# Control_Logic_V2.net
KiCad netlist of a schematic drawn in EAGLE
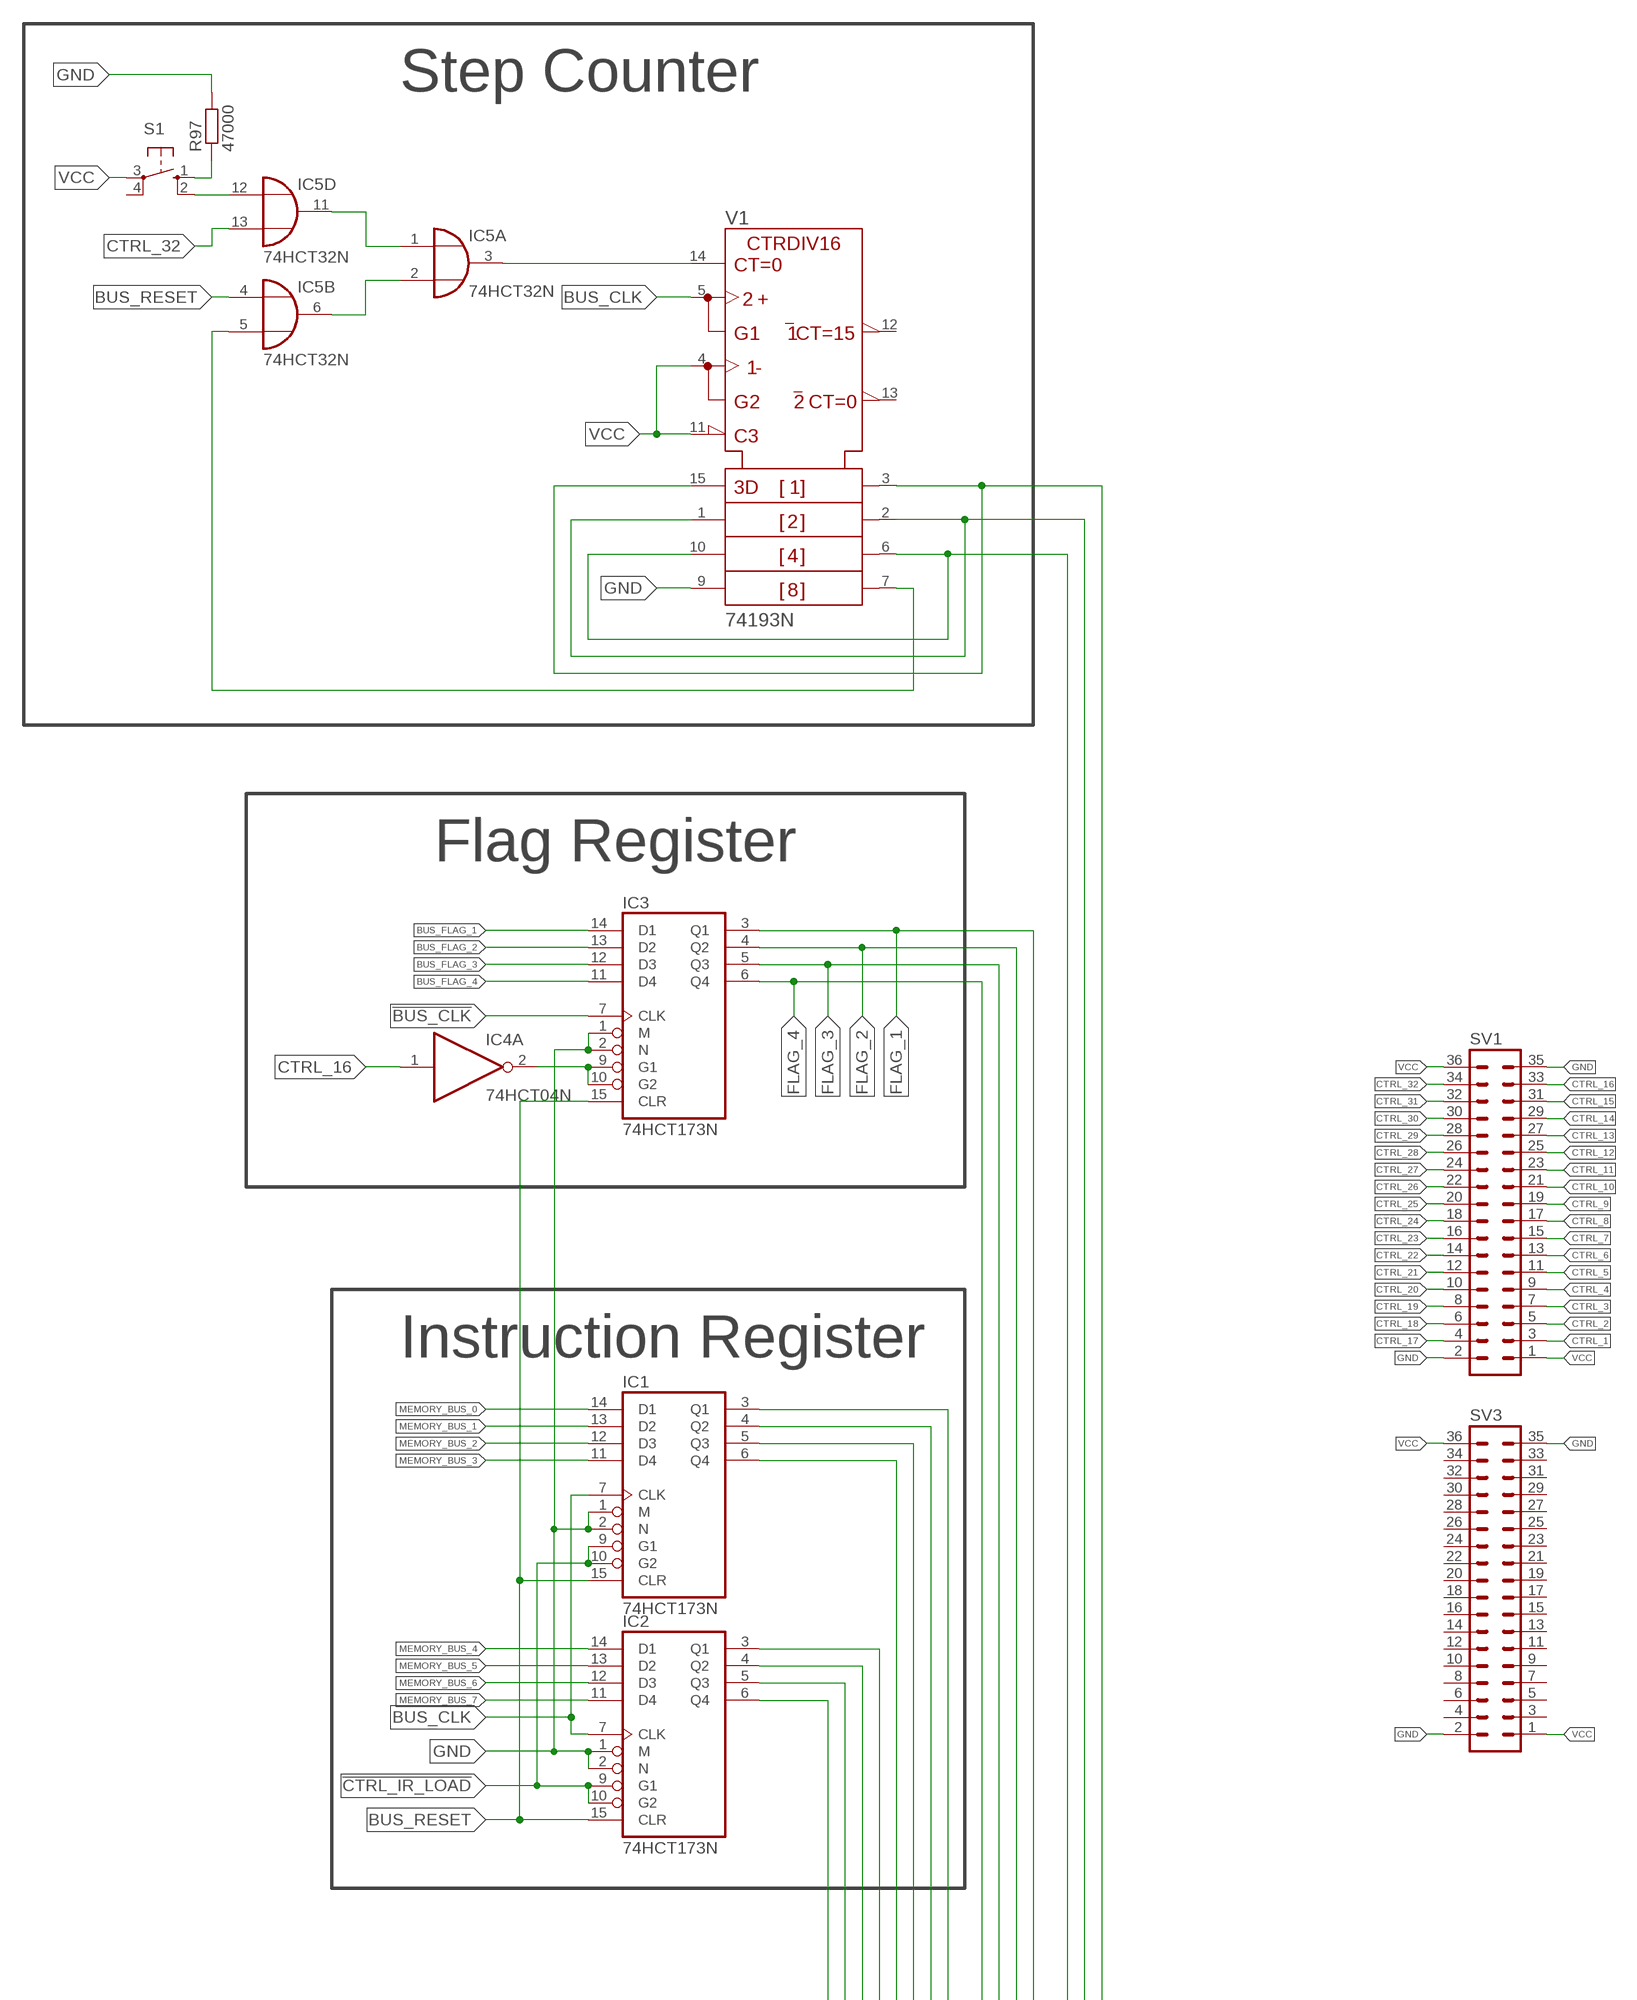
[diagram p0: schematic, sheet 1, part 1 of 3]
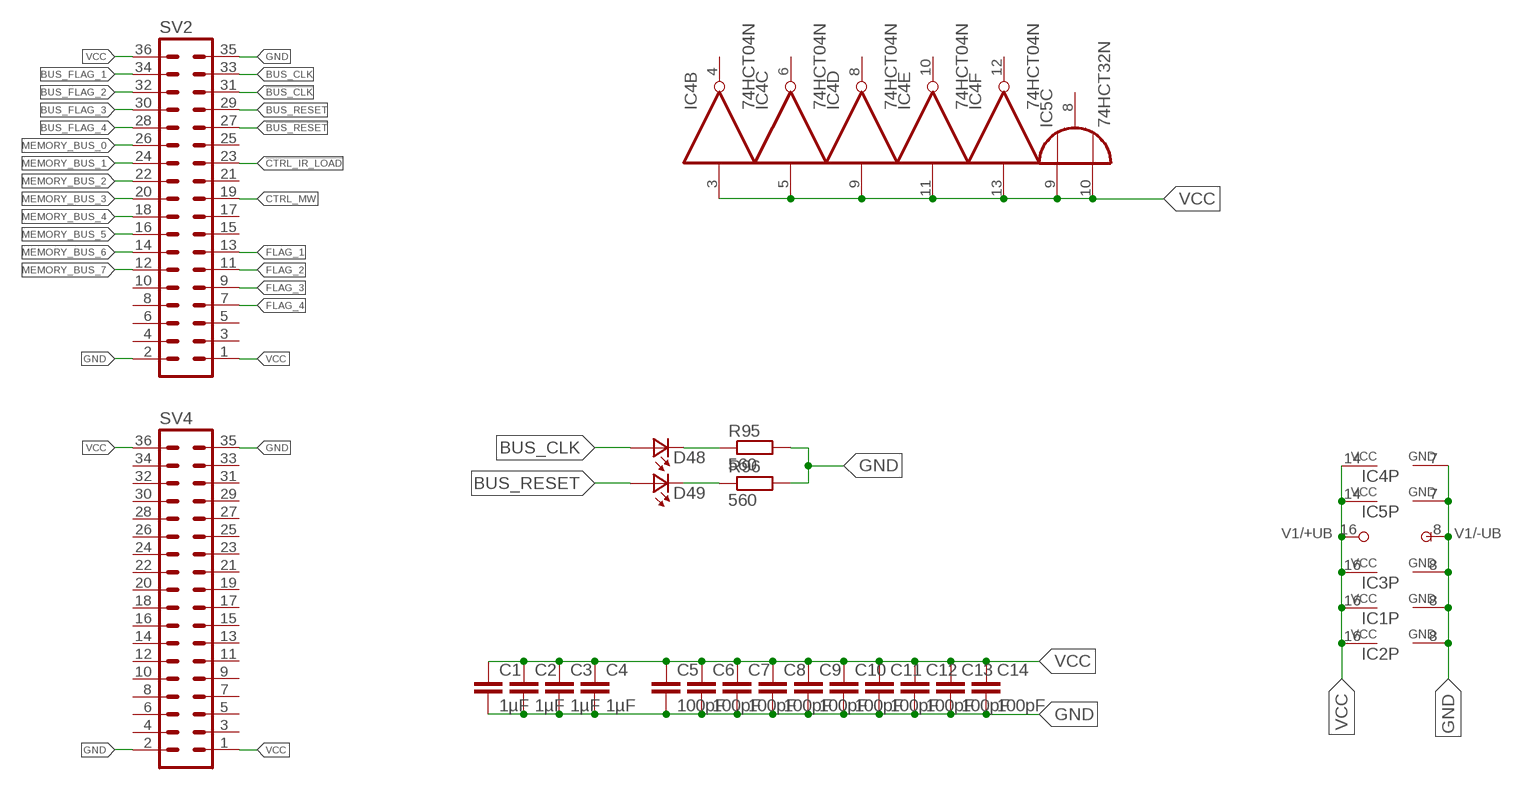
[diagram p1: schematic, sheet 1, part 2 of 3]
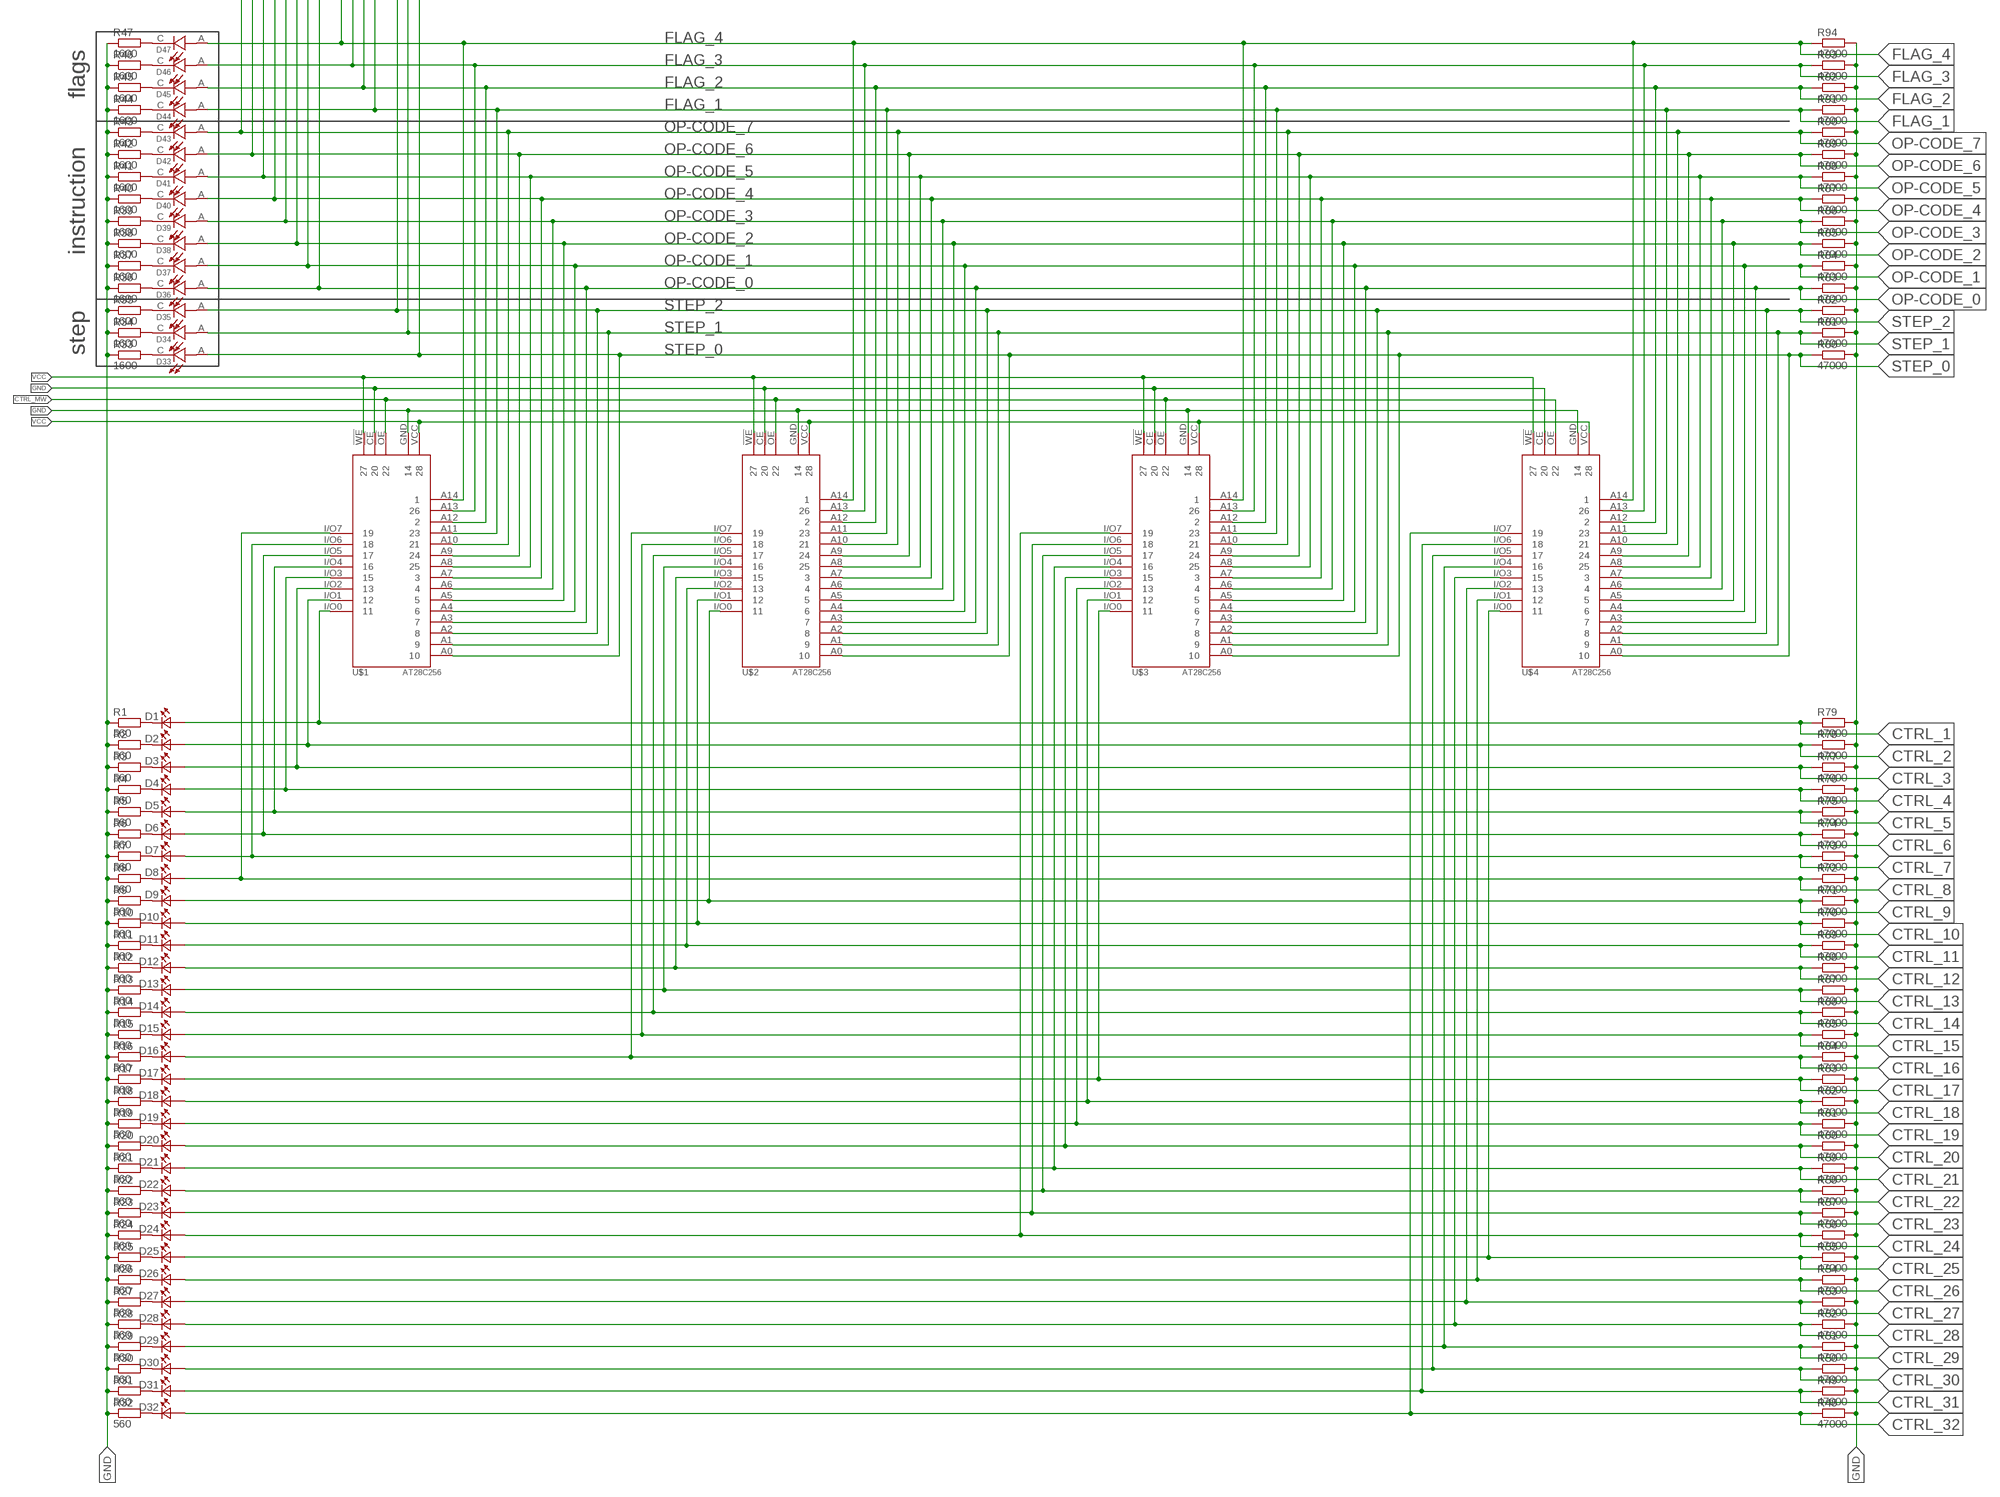
[diagram p2: schematic, sheet 1, part 3 of 3]

(export (version "E")
  (design (tool "Eeschema 10.0.6"))
  (components
    (comp (ref "C1")
      (value "1µF")
      (footprint "eagle-import:C0805")
      (libsource (lib "eagle-import") (part "C-EUC0805"))
    )
    (comp (ref "C2")
      (value "1µF")
      (footprint "eagle-import:C0805")
      (libsource (lib "eagle-import") (part "C-EUC0805"))
    )
    (comp (ref "C3")
      (value "1µF")
      (footprint "eagle-import:C0805")
      (libsource (lib "eagle-import") (part "C-EUC0805"))
    )
    (comp (ref "C4")
      (value "1µF")
      (footprint "eagle-import:C0805")
      (libsource (lib "eagle-import") (part "C-EUC0805"))
    )
    (comp (ref "C5")
      (value "100pF")
      (footprint "eagle-import:C0805")
      (libsource (lib "eagle-import") (part "C-EUC0805"))
    )
    (comp (ref "C6")
      (value "100pF")
      (footprint "eagle-import:C0805")
      (libsource (lib "eagle-import") (part "C-EUC0805"))
    )
    (comp (ref "C7")
      (value "100pF")
      (footprint "eagle-import:C0805")
      (libsource (lib "eagle-import") (part "C-EUC0805"))
    )
    (comp (ref "C8")
      (value "100pF")
      (footprint "eagle-import:C0805")
      (libsource (lib "eagle-import") (part "C-EUC0805"))
    )
    (comp (ref "C9")
      (value "100pF")
      (footprint "eagle-import:C0805")
      (libsource (lib "eagle-import") (part "C-EUC0805"))
    )
    (comp (ref "C10")
      (value "100pF")
      (footprint "eagle-import:C0805")
      (libsource (lib "eagle-import") (part "C-EUC0805"))
    )
    (comp (ref "C11")
      (value "100pF")
      (footprint "eagle-import:C0805")
      (libsource (lib "eagle-import") (part "C-EUC0805"))
    )
    (comp (ref "C12")
      (value "100pF")
      (footprint "eagle-import:C0805")
      (libsource (lib "eagle-import") (part "C-EUC0805"))
    )
    (comp (ref "C13")
      (value "100pF")
      (footprint "eagle-import:C0805")
      (libsource (lib "eagle-import") (part "C-EUC0805"))
    )
    (comp (ref "C14")
      (value "100pF")
      (footprint "eagle-import:C0805")
      (libsource (lib "eagle-import") (part "C-EUC0805"))
    )
    (comp (ref "D1")
      (value "LTST-C193TBKT-5A")
      (footprint "eagle-import:0603")
      (libsource (lib "eagle-import") (part "LTST-C193TBKT-5A"))
    )
    (comp (ref "D2")
      (value "LTST-C193TBKT-5A")
      (footprint "eagle-import:0603")
      (libsource (lib "eagle-import") (part "LTST-C193TBKT-5A"))
    )
    (comp (ref "D3")
      (value "LTST-C193TBKT-5A")
      (footprint "eagle-import:0603")
      (libsource (lib "eagle-import") (part "LTST-C193TBKT-5A"))
    )
    (comp (ref "D4")
      (value "LTST-C193TBKT-5A")
      (footprint "eagle-import:0603")
      (libsource (lib "eagle-import") (part "LTST-C193TBKT-5A"))
    )
    (comp (ref "D5")
      (value "LTST-C193TBKT-5A")
      (footprint "eagle-import:0603")
      (libsource (lib "eagle-import") (part "LTST-C193TBKT-5A"))
    )
    (comp (ref "D6")
      (value "LTST-C193TBKT-5A")
      (footprint "eagle-import:0603")
      (libsource (lib "eagle-import") (part "LTST-C193TBKT-5A"))
    )
    (comp (ref "D7")
      (value "LTST-C193TBKT-5A")
      (footprint "eagle-import:0603")
      (libsource (lib "eagle-import") (part "LTST-C193TBKT-5A"))
    )
    (comp (ref "D8")
      (value "LTST-C193TBKT-5A")
      (footprint "eagle-import:0603")
      (libsource (lib "eagle-import") (part "LTST-C193TBKT-5A"))
    )
    (comp (ref "D9")
      (value "LTST-C193TBKT-5A")
      (footprint "eagle-import:0603")
      (libsource (lib "eagle-import") (part "LTST-C193TBKT-5A"))
    )
    (comp (ref "D10")
      (value "LTST-C193TBKT-5A")
      (footprint "eagle-import:0603")
      (libsource (lib "eagle-import") (part "LTST-C193TBKT-5A"))
    )
    (comp (ref "D11")
      (value "LTST-C193TBKT-5A")
      (footprint "eagle-import:0603")
      (libsource (lib "eagle-import") (part "LTST-C193TBKT-5A"))
    )
    (comp (ref "D12")
      (value "LTST-C193TBKT-5A")
      (footprint "eagle-import:0603")
      (libsource (lib "eagle-import") (part "LTST-C193TBKT-5A"))
    )
    (comp (ref "D13")
      (value "LTST-C193TBKT-5A")
      (footprint "eagle-import:0603")
      (libsource (lib "eagle-import") (part "LTST-C193TBKT-5A"))
    )
    (comp (ref "D14")
      (value "LTST-C193TBKT-5A")
      (footprint "eagle-import:0603")
      (libsource (lib "eagle-import") (part "LTST-C193TBKT-5A"))
    )
    (comp (ref "D15")
      (value "LTST-C193TBKT-5A")
      (footprint "eagle-import:0603")
      (libsource (lib "eagle-import") (part "LTST-C193TBKT-5A"))
    )
    (comp (ref "D16")
      (value "LTST-C193TBKT-5A")
      (footprint "eagle-import:0603")
      (libsource (lib "eagle-import") (part "LTST-C193TBKT-5A"))
    )
    (comp (ref "D17")
      (value "LTST-C193TBKT-5A")
      (footprint "eagle-import:0603")
      (libsource (lib "eagle-import") (part "LTST-C193TBKT-5A"))
    )
    (comp (ref "D18")
      (value "LTST-C193TBKT-5A")
      (footprint "eagle-import:0603")
      (libsource (lib "eagle-import") (part "LTST-C193TBKT-5A"))
    )
    (comp (ref "D19")
      (value "LTST-C193TBKT-5A")
      (footprint "eagle-import:0603")
      (libsource (lib "eagle-import") (part "LTST-C193TBKT-5A"))
    )
    (comp (ref "D20")
      (value "LTST-C193TBKT-5A")
      (footprint "eagle-import:0603")
      (libsource (lib "eagle-import") (part "LTST-C193TBKT-5A"))
    )
    (comp (ref "D21")
      (value "LTST-C193TBKT-5A")
      (footprint "eagle-import:0603")
      (libsource (lib "eagle-import") (part "LTST-C193TBKT-5A"))
    )
    (comp (ref "D22")
      (value "LTST-C193TBKT-5A")
      (footprint "eagle-import:0603")
      (libsource (lib "eagle-import") (part "LTST-C193TBKT-5A"))
    )
    (comp (ref "D23")
      (value "LTST-C193TBKT-5A")
      (footprint "eagle-import:0603")
      (libsource (lib "eagle-import") (part "LTST-C193TBKT-5A"))
    )
    (comp (ref "D24")
      (value "LTST-C193TBKT-5A")
      (footprint "eagle-import:0603")
      (libsource (lib "eagle-import") (part "LTST-C193TBKT-5A"))
    )
    (comp (ref "D25")
      (value "LTST-C193TBKT-5A")
      (footprint "eagle-import:0603")
      (libsource (lib "eagle-import") (part "LTST-C193TBKT-5A"))
    )
    (comp (ref "D26")
      (value "LTST-C193TBKT-5A")
      (footprint "eagle-import:0603")
      (libsource (lib "eagle-import") (part "LTST-C193TBKT-5A"))
    )
    (comp (ref "D27")
      (value "LTST-C193TBKT-5A")
      (footprint "eagle-import:0603")
      (libsource (lib "eagle-import") (part "LTST-C193TBKT-5A"))
    )
    (comp (ref "D28")
      (value "LTST-C193TBKT-5A")
      (footprint "eagle-import:0603")
      (libsource (lib "eagle-import") (part "LTST-C193TBKT-5A"))
    )
    (comp (ref "D29")
      (value "LTST-C193TBKT-5A")
      (footprint "eagle-import:0603")
      (libsource (lib "eagle-import") (part "LTST-C193TBKT-5A"))
    )
    (comp (ref "D30")
      (value "LTST-C193TBKT-5A")
      (footprint "eagle-import:0603")
      (libsource (lib "eagle-import") (part "LTST-C193TBKT-5A"))
    )
    (comp (ref "D31")
      (value "LTST-C193TBKT-5A")
      (footprint "eagle-import:0603")
      (libsource (lib "eagle-import") (part "LTST-C193TBKT-5A"))
    )
    (comp (ref "D32")
      (value "LTST-C193TBKT-5A")
      (footprint "eagle-import:0603")
      (libsource (lib "eagle-import") (part "LTST-C193TBKT-5A"))
    )
    (comp (ref "D33")
      (value "LTST-C193KRKT-5A")
      (footprint "eagle-import:LEDC1608X45N")
      (fields (field (name "MANUFACTURER") "Lite-On"))
      (libsource (lib "eagle-import") (part "LTST-C193KRKT-5A"))
    )
    (comp (ref "D34")
      (value "LTST-C193KRKT-5A")
      (footprint "eagle-import:LEDC1608X45N")
      (fields (field (name "MANUFACTURER") "Lite-On"))
      (libsource (lib "eagle-import") (part "LTST-C193KRKT-5A"))
    )
    (comp (ref "D35")
      (value "LTST-C193KRKT-5A")
      (footprint "eagle-import:LEDC1608X45N")
      (fields (field (name "MANUFACTURER") "Lite-On"))
      (libsource (lib "eagle-import") (part "LTST-C193KRKT-5A"))
    )
    (comp (ref "D36")
      (value "LTST-C193KRKT-5A")
      (footprint "eagle-import:LEDC1608X45N")
      (fields (field (name "MANUFACTURER") "Lite-On"))
      (libsource (lib "eagle-import") (part "LTST-C193KRKT-5A"))
    )
    (comp (ref "D37")
      (value "LTST-C193KRKT-5A")
      (footprint "eagle-import:LEDC1608X45N")
      (fields (field (name "MANUFACTURER") "Lite-On"))
      (libsource (lib "eagle-import") (part "LTST-C193KRKT-5A"))
    )
    (comp (ref "D38")
      (value "LTST-C193KRKT-5A")
      (footprint "eagle-import:LEDC1608X45N")
      (fields (field (name "MANUFACTURER") "Lite-On"))
      (libsource (lib "eagle-import") (part "LTST-C193KRKT-5A"))
    )
    (comp (ref "D39")
      (value "LTST-C193KRKT-5A")
      (footprint "eagle-import:LEDC1608X45N")
      (fields (field (name "MANUFACTURER") "Lite-On"))
      (libsource (lib "eagle-import") (part "LTST-C193KRKT-5A"))
    )
    (comp (ref "D40")
      (value "LTST-C193KRKT-5A")
      (footprint "eagle-import:LEDC1608X45N")
      (fields (field (name "MANUFACTURER") "Lite-On"))
      (libsource (lib "eagle-import") (part "LTST-C193KRKT-5A"))
    )
    (comp (ref "D41")
      (value "LTST-C193KRKT-5A")
      (footprint "eagle-import:LEDC1608X45N")
      (fields (field (name "MANUFACTURER") "Lite-On"))
      (libsource (lib "eagle-import") (part "LTST-C193KRKT-5A"))
    )
    (comp (ref "D42")
      (value "LTST-C193KRKT-5A")
      (footprint "eagle-import:LEDC1608X45N")
      (fields (field (name "MANUFACTURER") "Lite-On"))
      (libsource (lib "eagle-import") (part "LTST-C193KRKT-5A"))
    )
    (comp (ref "D43")
      (value "LTST-C193KRKT-5A")
      (footprint "eagle-import:LEDC1608X45N")
      (fields (field (name "MANUFACTURER") "Lite-On"))
      (libsource (lib "eagle-import") (part "LTST-C193KRKT-5A"))
    )
    (comp (ref "D44")
      (value "LTST-C193KRKT-5A")
      (footprint "eagle-import:LEDC1608X45N")
      (fields (field (name "MANUFACTURER") "Lite-On"))
      (libsource (lib "eagle-import") (part "LTST-C193KRKT-5A"))
    )
    (comp (ref "D45")
      (value "LTST-C193KRKT-5A")
      (footprint "eagle-import:LEDC1608X45N")
      (fields (field (name "MANUFACTURER") "Lite-On"))
      (libsource (lib "eagle-import") (part "LTST-C193KRKT-5A"))
    )
    (comp (ref "D46")
      (value "LTST-C193KRKT-5A")
      (footprint "eagle-import:LEDC1608X45N")
      (fields (field (name "MANUFACTURER") "Lite-On"))
      (libsource (lib "eagle-import") (part "LTST-C193KRKT-5A"))
    )
    (comp (ref "D47")
      (value "LTST-C193KRKT-5A")
      (footprint "eagle-import:LEDC1608X45N")
      (fields (field (name "MANUFACTURER") "Lite-On"))
      (libsource (lib "eagle-import") (part "LTST-C193KRKT-5A"))
    )
    (comp (ref "D48")
      (value "LTST-C193TBKT-5A")
      (footprint "eagle-import:0603")
      (libsource (lib "eagle-import") (part "LTST-C193TBKT-5A"))
    )
    (comp (ref "D49")
      (value "LTST-C193TBKT-5A")
      (footprint "eagle-import:0603")
      (libsource (lib "eagle-import") (part "LTST-C193TBKT-5A"))
    )
    (comp (ref "IC1")
      (value "74HCT173N")
      (footprint "eagle-import:DIL16")
      (libsource (lib "eagle-import") (part "74173NHCT"))
    )
    (comp (ref "IC2")
      (value "74HCT173N")
      (footprint "eagle-import:DIL16")
      (libsource (lib "eagle-import") (part "74173NHCT"))
    )
    (comp (ref "IC3")
      (value "74HCT173N")
      (footprint "eagle-import:DIL16")
      (libsource (lib "eagle-import") (part "74173NHCT"))
    )
    (comp (ref "IC4")
      (value "74HCT04N")
      (footprint "eagle-import:DIL14")
      (libsource (lib "eagle-import") (part "7404NHCT"))
    )
    (comp (ref "IC5")
      (value "74HCT32N")
      (footprint "eagle-import:DIL14")
      (libsource (lib "eagle-import") (part "7432NHCT"))
    )
    (comp (ref "R1")
      (value "560")
      (footprint "eagle-import:R0805")
      (libsource (lib "eagle-import") (part "R-EU_R0805"))
    )
    (comp (ref "R2")
      (value "560")
      (footprint "eagle-import:R0805")
      (libsource (lib "eagle-import") (part "R-EU_R0805"))
    )
    (comp (ref "R3")
      (value "560")
      (footprint "eagle-import:R0805")
      (libsource (lib "eagle-import") (part "R-EU_R0805"))
    )
    (comp (ref "R4")
      (value "560")
      (footprint "eagle-import:R0805")
      (libsource (lib "eagle-import") (part "R-EU_R0805"))
    )
    (comp (ref "R5")
      (value "560")
      (footprint "eagle-import:R0805")
      (libsource (lib "eagle-import") (part "R-EU_R0805"))
    )
    (comp (ref "R6")
      (value "560")
      (footprint "eagle-import:R0805")
      (libsource (lib "eagle-import") (part "R-EU_R0805"))
    )
    (comp (ref "R7")
      (value "560")
      (footprint "eagle-import:R0805")
      (libsource (lib "eagle-import") (part "R-EU_R0805"))
    )
    (comp (ref "R8")
      (value "560")
      (footprint "eagle-import:R0805")
      (libsource (lib "eagle-import") (part "R-EU_R0805"))
    )
    (comp (ref "R9")
      (value "560")
      (footprint "eagle-import:R0805")
      (libsource (lib "eagle-import") (part "R-EU_R0805"))
    )
    (comp (ref "R10")
      (value "560")
      (footprint "eagle-import:R0805")
      (libsource (lib "eagle-import") (part "R-EU_R0805"))
    )
    (comp (ref "R11")
      (value "560")
      (footprint "eagle-import:R0805")
      (libsource (lib "eagle-import") (part "R-EU_R0805"))
    )
    (comp (ref "R12")
      (value "560")
      (footprint "eagle-import:R0805")
      (libsource (lib "eagle-import") (part "R-EU_R0805"))
    )
    (comp (ref "R13")
      (value "560")
      (footprint "eagle-import:R0805")
      (libsource (lib "eagle-import") (part "R-EU_R0805"))
    )
    (comp (ref "R14")
      (value "560")
      (footprint "eagle-import:R0805")
      (libsource (lib "eagle-import") (part "R-EU_R0805"))
    )
    (comp (ref "R15")
      (value "560")
      (footprint "eagle-import:R0805")
      (libsource (lib "eagle-import") (part "R-EU_R0805"))
    )
    (comp (ref "R16")
      (value "560")
      (footprint "eagle-import:R0805")
      (libsource (lib "eagle-import") (part "R-EU_R0805"))
    )
    (comp (ref "R17")
      (value "560")
      (footprint "eagle-import:R0805")
      (libsource (lib "eagle-import") (part "R-EU_R0805"))
    )
    (comp (ref "R18")
      (value "560")
      (footprint "eagle-import:R0805")
      (libsource (lib "eagle-import") (part "R-EU_R0805"))
    )
    (comp (ref "R19")
      (value "560")
      (footprint "eagle-import:R0805")
      (libsource (lib "eagle-import") (part "R-EU_R0805"))
    )
    (comp (ref "R20")
      (value "560")
      (footprint "eagle-import:R0805")
      (libsource (lib "eagle-import") (part "R-EU_R0805"))
    )
    (comp (ref "R21")
      (value "560")
      (footprint "eagle-import:R0805")
      (libsource (lib "eagle-import") (part "R-EU_R0805"))
    )
    (comp (ref "R22")
      (value "560")
      (footprint "eagle-import:R0805")
      (libsource (lib "eagle-import") (part "R-EU_R0805"))
    )
    (comp (ref "R23")
      (value "560")
      (footprint "eagle-import:R0805")
      (libsource (lib "eagle-import") (part "R-EU_R0805"))
    )
    (comp (ref "R24")
      (value "560")
      (footprint "eagle-import:R0805")
      (libsource (lib "eagle-import") (part "R-EU_R0805"))
    )
    (comp (ref "R25")
      (value "560")
      (footprint "eagle-import:R0805")
      (libsource (lib "eagle-import") (part "R-EU_R0805"))
    )
    (comp (ref "R26")
      (value "560")
      (footprint "eagle-import:R0805")
      (libsource (lib "eagle-import") (part "R-EU_R0805"))
    )
    (comp (ref "R27")
      (value "560")
      (footprint "eagle-import:R0805")
      (libsource (lib "eagle-import") (part "R-EU_R0805"))
    )
    (comp (ref "R28")
      (value "560")
      (footprint "eagle-import:R0805")
      (libsource (lib "eagle-import") (part "R-EU_R0805"))
    )
    (comp (ref "R29")
      (value "560")
      (footprint "eagle-import:R0805")
      (libsource (lib "eagle-import") (part "R-EU_R0805"))
    )
    (comp (ref "R30")
      (value "560")
      (footprint "eagle-import:R0805")
      (libsource (lib "eagle-import") (part "R-EU_R0805"))
    )
    (comp (ref "R31")
      (value "560")
      (footprint "eagle-import:R0805")
      (libsource (lib "eagle-import") (part "R-EU_R0805"))
    )
    (comp (ref "R32")
      (value "560")
      (footprint "eagle-import:R0805")
      (libsource (lib "eagle-import") (part "R-EU_R0805"))
    )
    (comp (ref "R33")
      (value "1600")
      (footprint "eagle-import:R0805")
      (libsource (lib "eagle-import") (part "R-EU_R0805"))
    )
    (comp (ref "R34")
      (value "1600")
      (footprint "eagle-import:R0805")
      (libsource (lib "eagle-import") (part "R-EU_R0805"))
    )
    (comp (ref "R35")
      (value "1600")
      (footprint "eagle-import:R0805")
      (libsource (lib "eagle-import") (part "R-EU_R0805"))
    )
    (comp (ref "R36")
      (value "1600")
      (footprint "eagle-import:R0805")
      (libsource (lib "eagle-import") (part "R-EU_R0805"))
    )
    (comp (ref "R37")
      (value "1600")
      (footprint "eagle-import:R0805")
      (libsource (lib "eagle-import") (part "R-EU_R0805"))
    )
    (comp (ref "R38")
      (value "1600")
      (footprint "eagle-import:R0805")
      (libsource (lib "eagle-import") (part "R-EU_R0805"))
    )
    (comp (ref "R39")
      (value "1600")
      (footprint "eagle-import:R0805")
      (libsource (lib "eagle-import") (part "R-EU_R0805"))
    )
    (comp (ref "R40")
      (value "1600")
      (footprint "eagle-import:R0805")
      (libsource (lib "eagle-import") (part "R-EU_R0805"))
    )
    (comp (ref "R41")
      (value "1600")
      (footprint "eagle-import:R0805")
      (libsource (lib "eagle-import") (part "R-EU_R0805"))
    )
    (comp (ref "R42")
      (value "1600")
      (footprint "eagle-import:R0805")
      (libsource (lib "eagle-import") (part "R-EU_R0805"))
    )
    (comp (ref "R43")
      (value "1600")
      (footprint "eagle-import:R0805")
      (libsource (lib "eagle-import") (part "R-EU_R0805"))
    )
    (comp (ref "R44")
      (value "1600")
      (footprint "eagle-import:R0805")
      (libsource (lib "eagle-import") (part "R-EU_R0805"))
    )
    (comp (ref "R45")
      (value "1600")
      (footprint "eagle-import:R0805")
      (libsource (lib "eagle-import") (part "R-EU_R0805"))
    )
    (comp (ref "R46")
      (value "1600")
      (footprint "eagle-import:R0805")
      (libsource (lib "eagle-import") (part "R-EU_R0805"))
    )
    (comp (ref "R47")
      (value "1600")
      (footprint "eagle-import:R0805")
      (libsource (lib "eagle-import") (part "R-EU_R0805"))
    )
    (comp (ref "R48")
      (value "47000")
      (footprint "eagle-import:R0805")
      (libsource (lib "eagle-import") (part "R-EU_R0805"))
    )
    (comp (ref "R49")
      (value "47000")
      (footprint "eagle-import:R0805")
      (libsource (lib "eagle-import") (part "R-EU_R0805"))
    )
    (comp (ref "R50")
      (value "47000")
      (footprint "eagle-import:R0805")
      (libsource (lib "eagle-import") (part "R-EU_R0805"))
    )
    (comp (ref "R51")
      (value "47000")
      (footprint "eagle-import:R0805")
      (libsource (lib "eagle-import") (part "R-EU_R0805"))
    )
    (comp (ref "R52")
      (value "47000")
      (footprint "eagle-import:R0805")
      (libsource (lib "eagle-import") (part "R-EU_R0805"))
    )
    (comp (ref "R53")
      (value "47000")
      (footprint "eagle-import:R0805")
      (libsource (lib "eagle-import") (part "R-EU_R0805"))
    )
    (comp (ref "R54")
      (value "47000")
      (footprint "eagle-import:R0805")
      (libsource (lib "eagle-import") (part "R-EU_R0805"))
    )
    (comp (ref "R55")
      (value "47000")
      (footprint "eagle-import:R0805")
      (libsource (lib "eagle-import") (part "R-EU_R0805"))
    )
    (comp (ref "R56")
      (value "47000")
      (footprint "eagle-import:R0805")
      (libsource (lib "eagle-import") (part "R-EU_R0805"))
    )
    (comp (ref "R57")
      (value "47000")
      (footprint "eagle-import:R0805")
      (libsource (lib "eagle-import") (part "R-EU_R0805"))
    )
    (comp (ref "R58")
      (value "47000")
      (footprint "eagle-import:R0805")
      (libsource (lib "eagle-import") (part "R-EU_R0805"))
    )
    (comp (ref "R59")
      (value "47000")
      (footprint "eagle-import:R0805")
      (libsource (lib "eagle-import") (part "R-EU_R0805"))
    )
    (comp (ref "R60")
      (value "47000")
      (footprint "eagle-import:R0805")
      (libsource (lib "eagle-import") (part "R-EU_R0805"))
    )
    (comp (ref "R61")
      (value "47000")
      (footprint "eagle-import:R0805")
      (libsource (lib "eagle-import") (part "R-EU_R0805"))
    )
    (comp (ref "R62")
      (value "47000")
      (footprint "eagle-import:R0805")
      (libsource (lib "eagle-import") (part "R-EU_R0805"))
    )
    (comp (ref "R63")
      (value "47000")
      (footprint "eagle-import:R0805")
      (libsource (lib "eagle-import") (part "R-EU_R0805"))
    )
    (comp (ref "R64")
      (value "47000")
      (footprint "eagle-import:R0805")
      (libsource (lib "eagle-import") (part "R-EU_R0805"))
    )
    (comp (ref "R65")
      (value "47000")
      (footprint "eagle-import:R0805")
      (libsource (lib "eagle-import") (part "R-EU_R0805"))
    )
    (comp (ref "R66")
      (value "47000")
      (footprint "eagle-import:R0805")
      (libsource (lib "eagle-import") (part "R-EU_R0805"))
    )
    (comp (ref "R67")
      (value "47000")
      (footprint "eagle-import:R0805")
      (libsource (lib "eagle-import") (part "R-EU_R0805"))
    )
    (comp (ref "R68")
      (value "47000")
      (footprint "eagle-import:R0805")
      (libsource (lib "eagle-import") (part "R-EU_R0805"))
    )
    (comp (ref "R69")
      (value "47000")
      (footprint "eagle-import:R0805")
      (libsource (lib "eagle-import") (part "R-EU_R0805"))
    )
    (comp (ref "R70")
      (value "47000")
      (footprint "eagle-import:R0805")
      (libsource (lib "eagle-import") (part "R-EU_R0805"))
    )
    (comp (ref "R71")
      (value "47000")
      (footprint "eagle-import:R0805")
      (libsource (lib "eagle-import") (part "R-EU_R0805"))
    )
    (comp (ref "R72")
      (value "47000")
      (footprint "eagle-import:R0805")
      (libsource (lib "eagle-import") (part "R-EU_R0805"))
    )
    (comp (ref "R73")
      (value "47000")
      (footprint "eagle-import:R0805")
      (libsource (lib "eagle-import") (part "R-EU_R0805"))
    )
    (comp (ref "R74")
      (value "47000")
      (footprint "eagle-import:R0805")
      (libsource (lib "eagle-import") (part "R-EU_R0805"))
    )
    (comp (ref "R75")
      (value "47000")
      (footprint "eagle-import:R0805")
      (libsource (lib "eagle-import") (part "R-EU_R0805"))
    )
    (comp (ref "R76")
      (value "47000")
      (footprint "eagle-import:R0805")
      (libsource (lib "eagle-import") (part "R-EU_R0805"))
    )
    (comp (ref "R77")
      (value "47000")
      (footprint "eagle-import:R0805")
      (libsource (lib "eagle-import") (part "R-EU_R0805"))
    )
    (comp (ref "R78")
      (value "47000")
      (footprint "eagle-import:R0805")
      (libsource (lib "eagle-import") (part "R-EU_R0805"))
    )
    (comp (ref "R79")
      (value "47000")
      (footprint "eagle-import:R0805")
      (libsource (lib "eagle-import") (part "R-EU_R0805"))
    )
    (comp (ref "R80")
      (value "47000")
      (footprint "eagle-import:R0805")
      (libsource (lib "eagle-import") (part "R-EU_R0805"))
    )
    (comp (ref "R81")
      (value "47000")
      (footprint "eagle-import:R0805")
      (libsource (lib "eagle-import") (part "R-EU_R0805"))
    )
    (comp (ref "R82")
      (value "47000")
      (footprint "eagle-import:R0805")
      (libsource (lib "eagle-import") (part "R-EU_R0805"))
    )
    (comp (ref "R83")
      (value "47000")
      (footprint "eagle-import:R0805")
      (libsource (lib "eagle-import") (part "R-EU_R0805"))
    )
    (comp (ref "R84")
      (value "47000")
      (footprint "eagle-import:R0805")
      (libsource (lib "eagle-import") (part "R-EU_R0805"))
    )
    (comp (ref "R85")
      (value "47000")
      (footprint "eagle-import:R0805")
      (libsource (lib "eagle-import") (part "R-EU_R0805"))
    )
    (comp (ref "R86")
      (value "47000")
      (footprint "eagle-import:R0805")
      (libsource (lib "eagle-import") (part "R-EU_R0805"))
    )
    (comp (ref "R87")
      (value "47000")
      (footprint "eagle-import:R0805")
      (libsource (lib "eagle-import") (part "R-EU_R0805"))
    )
    (comp (ref "R88")
      (value "47000")
      (footprint "eagle-import:R0805")
      (libsource (lib "eagle-import") (part "R-EU_R0805"))
    )
    (comp (ref "R89")
      (value "47000")
      (footprint "eagle-import:R0805")
      (libsource (lib "eagle-import") (part "R-EU_R0805"))
    )
    (comp (ref "R90")
      (value "47000")
      (footprint "eagle-import:R0805")
      (libsource (lib "eagle-import") (part "R-EU_R0805"))
    )
    (comp (ref "R91")
      (value "47000")
      (footprint "eagle-import:R0805")
      (libsource (lib "eagle-import") (part "R-EU_R0805"))
    )
    (comp (ref "R92")
      (value "47000")
      (footprint "eagle-import:R0805")
      (libsource (lib "eagle-import") (part "R-EU_R0805"))
    )
    (comp (ref "R93")
      (value "47000")
      (footprint "eagle-import:R0805")
      (libsource (lib "eagle-import") (part "R-EU_R0805"))
    )
    (comp (ref "R94")
      (value "47000")
      (footprint "eagle-import:R0805")
      (libsource (lib "eagle-import") (part "R-EU_R0805"))
    )
    (comp (ref "R95")
      (value "560")
      (footprint "eagle-import:R0805")
      (libsource (lib "eagle-import") (part "R-EU_R0805"))
    )
    (comp (ref "R96")
      (value "560")
      (footprint "eagle-import:R0805")
      (libsource (lib "eagle-import") (part "R-EU_R0805"))
    )
    (comp (ref "R97")
      (value "47000")
      (footprint "eagle-import:R0805")
      (libsource (lib "eagle-import") (part "R-EU_R0805"))
    )
    (comp (ref "S1")
      (value "10-XX")
      (footprint "eagle-import:B3F-10XX")
      (fields (field (name "MPN") "B3F-1000"))
      (libsource (lib "eagle-import") (part "10-XX"))
    )
    (comp (ref "SV1")
      (value "MA18-2")
      (footprint "eagle-import:MA18-2")
      (libsource (lib "eagle-import") (part "MA18-2"))
    )
    (comp (ref "SV2")
      (value "MA18-2")
      (footprint "eagle-import:MA18-2")
      (libsource (lib "eagle-import") (part "MA18-2"))
    )
    (comp (ref "SV3")
      (value "MA18-2")
      (footprint "eagle-import:MA18-2")
      (libsource (lib "eagle-import") (part "MA18-2"))
    )
    (comp (ref "SV4")
      (value "MA18-2")
      (footprint "eagle-import:MA18-2")
      (libsource (lib "eagle-import") (part "MA18-2"))
    )
    (comp (ref "U$1")
      (value "AT28C256")
      (footprint "eagle-import:AT28C256")
      (libsource (lib "eagle-import") (part "AT28C256"))
    )
    (comp (ref "U$2")
      (value "AT28C256")
      (footprint "eagle-import:AT28C256")
      (libsource (lib "eagle-import") (part "AT28C256"))
    )
    (comp (ref "U$3")
      (value "AT28C256")
      (footprint "eagle-import:AT28C256")
      (libsource (lib "eagle-import") (part "AT28C256"))
    )
    (comp (ref "U$4")
      (value "AT28C256")
      (footprint "eagle-import:AT28C256")
      (libsource (lib "eagle-import") (part "AT28C256"))
    )
    (comp (ref "V1")
      (value "74193N")
      (footprint "eagle-import:DIL16")
      (libsource (lib "eagle-import") (part "74193N"))
    )
  )
  (nets
    (net (code "1") (name "/~{BUS_CLK}") (class "Default")
      (node (ref "IC3") (pin "7") (pinfunction "CLK_7") (pintype "input"))
      (node (ref "SV2") (pin "31") (pinfunction "31_31") (pintype "passive"))
    )
    (net (code "2") (name "/~{BUS_RESET}") (class "Default")
      (node (ref "SV2") (pin "27") (pinfunction "27_27") (pintype "passive"))
    )
    (net (code "3") (name "/~{CTRL_IR_LOAD}") (class "Default")
      (node (ref "IC1") (pin "10") (pinfunction "G2_10") (pintype "input"))
      (node (ref "IC1") (pin "9") (pinfunction "G1_9") (pintype "input"))
      (node (ref "IC2") (pin "10") (pinfunction "G2_10") (pintype "input"))
      (node (ref "IC2") (pin "9") (pinfunction "G1_9") (pintype "input"))
      (node (ref "SV2") (pin "23") (pinfunction "23_23") (pintype "passive"))
    )
    (net (code "4") (name "BUS_CLK") (class "Default")
      (node (ref "D48") (pin "2") (pinfunction "A2_2") (pintype "passive"))
      (node (ref "IC1") (pin "7") (pinfunction "CLK_7") (pintype "input"))
      (node (ref "IC2") (pin "7") (pinfunction "CLK_7") (pintype "input"))
      (node (ref "SV2") (pin "33") (pinfunction "33_33") (pintype "passive"))
      (node (ref "V1") (pin "5") (pinfunction "UP_5") (pintype "input"))
    )
    (net (code "5") (name "BUS_FLAG_1") (class "Default")
      (node (ref "IC3") (pin "14") (pinfunction "D1_14") (pintype "input"))
      (node (ref "SV2") (pin "34") (pinfunction "34_34") (pintype "passive"))
    )
    (net (code "6") (name "BUS_FLAG_2") (class "Default")
      (node (ref "IC3") (pin "13") (pinfunction "D2_13") (pintype "input"))
      (node (ref "SV2") (pin "32") (pinfunction "32_32") (pintype "passive"))
    )
    (net (code "7") (name "BUS_FLAG_3") (class "Default")
      (node (ref "IC3") (pin "12") (pinfunction "D3_12") (pintype "input"))
      (node (ref "SV2") (pin "30") (pinfunction "30_30") (pintype "passive"))
    )
    (net (code "8") (name "BUS_FLAG_4") (class "Default")
      (node (ref "IC3") (pin "11") (pinfunction "D4_11") (pintype "input"))
      (node (ref "SV2") (pin "28") (pinfunction "28_28") (pintype "passive"))
    )
    (net (code "9") (name "BUS_RESET") (class "Default")
      (node (ref "D49") (pin "2") (pinfunction "A2_2") (pintype "passive"))
      (node (ref "IC1") (pin "15") (pinfunction "CLR_15") (pintype "input"))
      (node (ref "IC2") (pin "15") (pinfunction "CLR_15") (pintype "input"))
      (node (ref "IC3") (pin "15") (pinfunction "CLR_15") (pintype "input"))
      (node (ref "IC5") (pin "4") (pinfunction "I0_4") (pintype "input"))
      (node (ref "SV2") (pin "29") (pinfunction "29_29") (pintype "passive"))
    )
    (net (code "10") (name "CTRL_1") (class "Default")
      (node (ref "D1") (pin "2") (pinfunction "A2_2") (pintype "passive"))
      (node (ref "R79") (pin "1") (pinfunction "1_1") (pintype "passive"))
      (node (ref "SV1") (pin "3") (pinfunction "3_3") (pintype "passive"))
      (node (ref "U$1") (pin "I/O0") (pinfunction "11_I/O0") (pintype "bidirectional"))
    )
    (net (code "11") (name "CTRL_2") (class "Default")
      (node (ref "D2") (pin "2") (pinfunction "A2_2") (pintype "passive"))
      (node (ref "R78") (pin "1") (pinfunction "1_1") (pintype "passive"))
      (node (ref "SV1") (pin "5") (pinfunction "5_5") (pintype "passive"))
      (node (ref "U$1") (pin "I/O1") (pinfunction "12_I/O1") (pintype "bidirectional"))
    )
    (net (code "12") (name "CTRL_3") (class "Default")
      (node (ref "D3") (pin "2") (pinfunction "A2_2") (pintype "passive"))
      (node (ref "R77") (pin "1") (pinfunction "1_1") (pintype "passive"))
      (node (ref "SV1") (pin "7") (pinfunction "7_7") (pintype "passive"))
      (node (ref "U$1") (pin "I/O2") (pinfunction "13_I/O2") (pintype "bidirectional"))
    )
    (net (code "13") (name "CTRL_4") (class "Default")
      (node (ref "D4") (pin "2") (pinfunction "A2_2") (pintype "passive"))
      (node (ref "R76") (pin "1") (pinfunction "1_1") (pintype "passive"))
      (node (ref "SV1") (pin "9") (pinfunction "9_9") (pintype "passive"))
      (node (ref "U$1") (pin "I/O3") (pinfunction "15_I/O3") (pintype "bidirectional"))
    )
    (net (code "14") (name "CTRL_5") (class "Default")
      (node (ref "D5") (pin "2") (pinfunction "A2_2") (pintype "passive"))
      (node (ref "R75") (pin "1") (pinfunction "1_1") (pintype "passive"))
      (node (ref "SV1") (pin "11") (pinfunction "11_11") (pintype "passive"))
      (node (ref "U$1") (pin "I/O4") (pinfunction "16_I/O4") (pintype "bidirectional"))
    )
    (net (code "15") (name "CTRL_6") (class "Default")
      (node (ref "D6") (pin "2") (pinfunction "A2_2") (pintype "passive"))
      (node (ref "R74") (pin "1") (pinfunction "1_1") (pintype "passive"))
      (node (ref "SV1") (pin "13") (pinfunction "13_13") (pintype "passive"))
      (node (ref "U$1") (pin "I/O5") (pinfunction "17_I/O5") (pintype "bidirectional"))
    )
    (net (code "16") (name "CTRL_7") (class "Default")
      (node (ref "D7") (pin "2") (pinfunction "A2_2") (pintype "passive"))
      (node (ref "R73") (pin "1") (pinfunction "1_1") (pintype "passive"))
      (node (ref "SV1") (pin "15") (pinfunction "15_15") (pintype "passive"))
      (node (ref "U$1") (pin "I/O6") (pinfunction "18_I/O6") (pintype "bidirectional"))
    )
    (net (code "17") (name "CTRL_8") (class "Default")
      (node (ref "D8") (pin "2") (pinfunction "A2_2") (pintype "passive"))
      (node (ref "R72") (pin "1") (pinfunction "1_1") (pintype "passive"))
      (node (ref "SV1") (pin "17") (pinfunction "17_17") (pintype "passive"))
      (node (ref "U$1") (pin "I/O7") (pinfunction "19_I/O7") (pintype "bidirectional"))
    )
    (net (code "18") (name "CTRL_9") (class "Default")
      (node (ref "D9") (pin "2") (pinfunction "A2_2") (pintype "passive"))
      (node (ref "R71") (pin "1") (pinfunction "1_1") (pintype "passive"))
      (node (ref "SV1") (pin "19") (pinfunction "19_19") (pintype "passive"))
      (node (ref "U$2") (pin "I/O0") (pinfunction "11_I/O0") (pintype "bidirectional"))
    )
    (net (code "19") (name "CTRL_10") (class "Default")
      (node (ref "D10") (pin "2") (pinfunction "A2_2") (pintype "passive"))
      (node (ref "R70") (pin "1") (pinfunction "1_1") (pintype "passive"))
      (node (ref "SV1") (pin "21") (pinfunction "21_21") (pintype "passive"))
      (node (ref "U$2") (pin "I/O1") (pinfunction "12_I/O1") (pintype "bidirectional"))
    )
    (net (code "20") (name "CTRL_11") (class "Default")
      (node (ref "D11") (pin "2") (pinfunction "A2_2") (pintype "passive"))
      (node (ref "R69") (pin "1") (pinfunction "1_1") (pintype "passive"))
      (node (ref "SV1") (pin "23") (pinfunction "23_23") (pintype "passive"))
      (node (ref "U$2") (pin "I/O2") (pinfunction "13_I/O2") (pintype "bidirectional"))
    )
    (net (code "21") (name "CTRL_12") (class "Default")
      (node (ref "D12") (pin "2") (pinfunction "A2_2") (pintype "passive"))
      (node (ref "R68") (pin "1") (pinfunction "1_1") (pintype "passive"))
      (node (ref "SV1") (pin "25") (pinfunction "25_25") (pintype "passive"))
      (node (ref "U$2") (pin "I/O3") (pinfunction "15_I/O3") (pintype "bidirectional"))
    )
    (net (code "22") (name "CTRL_13") (class "Default")
      (node (ref "D13") (pin "2") (pinfunction "A2_2") (pintype "passive"))
      (node (ref "R67") (pin "1") (pinfunction "1_1") (pintype "passive"))
      (node (ref "SV1") (pin "27") (pinfunction "27_27") (pintype "passive"))
      (node (ref "U$2") (pin "I/O4") (pinfunction "16_I/O4") (pintype "bidirectional"))
    )
    (net (code "23") (name "CTRL_14") (class "Default")
      (node (ref "D14") (pin "2") (pinfunction "A2_2") (pintype "passive"))
      (node (ref "R66") (pin "1") (pinfunction "1_1") (pintype "passive"))
      (node (ref "SV1") (pin "29") (pinfunction "29_29") (pintype "passive"))
      (node (ref "U$2") (pin "I/O5") (pinfunction "17_I/O5") (pintype "bidirectional"))
    )
    (net (code "24") (name "CTRL_15") (class "Default")
      (node (ref "D15") (pin "2") (pinfunction "A2_2") (pintype "passive"))
      (node (ref "R65") (pin "1") (pinfunction "1_1") (pintype "passive"))
      (node (ref "SV1") (pin "31") (pinfunction "31_31") (pintype "passive"))
      (node (ref "U$2") (pin "I/O6") (pinfunction "18_I/O6") (pintype "bidirectional"))
    )
    (net (code "25") (name "CTRL_16") (class "Default")
      (node (ref "D16") (pin "2") (pinfunction "A2_2") (pintype "passive"))
      (node (ref "IC4") (pin "1") (pinfunction "I_1") (pintype "input"))
      (node (ref "R64") (pin "1") (pinfunction "1_1") (pintype "passive"))
      (node (ref "SV1") (pin "33") (pinfunction "33_33") (pintype "passive"))
      (node (ref "U$2") (pin "I/O7") (pinfunction "19_I/O7") (pintype "bidirectional"))
    )
    (net (code "26") (name "CTRL_17") (class "Default")
      (node (ref "D17") (pin "2") (pinfunction "A2_2") (pintype "passive"))
      (node (ref "R63") (pin "1") (pinfunction "1_1") (pintype "passive"))
      (node (ref "SV1") (pin "4") (pinfunction "4_4") (pintype "passive"))
      (node (ref "U$3") (pin "I/O0") (pinfunction "11_I/O0") (pintype "bidirectional"))
    )
    (net (code "27") (name "CTRL_18") (class "Default")
      (node (ref "D18") (pin "2") (pinfunction "A2_2") (pintype "passive"))
      (node (ref "R62") (pin "1") (pinfunction "1_1") (pintype "passive"))
      (node (ref "SV1") (pin "6") (pinfunction "6_6") (pintype "passive"))
      (node (ref "U$3") (pin "I/O1") (pinfunction "12_I/O1") (pintype "bidirectional"))
    )
    (net (code "28") (name "CTRL_19") (class "Default")
      (node (ref "D19") (pin "2") (pinfunction "A2_2") (pintype "passive"))
      (node (ref "R61") (pin "1") (pinfunction "1_1") (pintype "passive"))
      (node (ref "SV1") (pin "8") (pinfunction "8_8") (pintype "passive"))
      (node (ref "U$3") (pin "I/O2") (pinfunction "13_I/O2") (pintype "bidirectional"))
    )
    (net (code "29") (name "CTRL_20") (class "Default")
      (node (ref "D20") (pin "2") (pinfunction "A2_2") (pintype "passive"))
      (node (ref "R60") (pin "1") (pinfunction "1_1") (pintype "passive"))
      (node (ref "SV1") (pin "10") (pinfunction "10_10") (pintype "passive"))
      (node (ref "U$3") (pin "I/O3") (pinfunction "15_I/O3") (pintype "bidirectional"))
    )
    (net (code "30") (name "CTRL_21") (class "Default")
      (node (ref "D21") (pin "2") (pinfunction "A2_2") (pintype "passive"))
      (node (ref "R59") (pin "1") (pinfunction "1_1") (pintype "passive"))
      (node (ref "SV1") (pin "12") (pinfunction "12_12") (pintype "passive"))
      (node (ref "U$3") (pin "I/O4") (pinfunction "16_I/O4") (pintype "bidirectional"))
    )
    (net (code "31") (name "CTRL_22") (class "Default")
      (node (ref "D22") (pin "2") (pinfunction "A2_2") (pintype "passive"))
      (node (ref "R58") (pin "1") (pinfunction "1_1") (pintype "passive"))
      (node (ref "SV1") (pin "14") (pinfunction "14_14") (pintype "passive"))
      (node (ref "U$3") (pin "I/O5") (pinfunction "17_I/O5") (pintype "bidirectional"))
    )
    (net (code "32") (name "CTRL_23") (class "Default")
      (node (ref "D23") (pin "2") (pinfunction "A2_2") (pintype "passive"))
      (node (ref "R57") (pin "1") (pinfunction "1_1") (pintype "passive"))
      (node (ref "SV1") (pin "16") (pinfunction "16_16") (pintype "passive"))
      (node (ref "U$3") (pin "I/O6") (pinfunction "18_I/O6") (pintype "bidirectional"))
    )
    (net (code "33") (name "CTRL_24") (class "Default")
      (node (ref "D24") (pin "2") (pinfunction "A2_2") (pintype "passive"))
      (node (ref "R56") (pin "1") (pinfunction "1_1") (pintype "passive"))
      (node (ref "SV1") (pin "18") (pinfunction "18_18") (pintype "passive"))
      (node (ref "U$3") (pin "I/O7") (pinfunction "19_I/O7") (pintype "bidirectional"))
    )
    (net (code "34") (name "CTRL_25") (class "Default")
      (node (ref "D25") (pin "2") (pinfunction "A2_2") (pintype "passive"))
      (node (ref "R55") (pin "1") (pinfunction "1_1") (pintype "passive"))
      (node (ref "SV1") (pin "20") (pinfunction "20_20") (pintype "passive"))
      (node (ref "U$4") (pin "I/O0") (pinfunction "11_I/O0") (pintype "bidirectional"))
    )
    (net (code "35") (name "CTRL_26") (class "Default")
      (node (ref "D26") (pin "2") (pinfunction "A2_2") (pintype "passive"))
      (node (ref "R54") (pin "1") (pinfunction "1_1") (pintype "passive"))
      (node (ref "SV1") (pin "22") (pinfunction "22_22") (pintype "passive"))
      (node (ref "U$4") (pin "I/O1") (pinfunction "12_I/O1") (pintype "bidirectional"))
    )
    (net (code "36") (name "CTRL_27") (class "Default")
      (node (ref "D27") (pin "2") (pinfunction "A2_2") (pintype "passive"))
      (node (ref "R53") (pin "1") (pinfunction "1_1") (pintype "passive"))
      (node (ref "SV1") (pin "24") (pinfunction "24_24") (pintype "passive"))
      (node (ref "U$4") (pin "I/O2") (pinfunction "13_I/O2") (pintype "bidirectional"))
    )
    (net (code "37") (name "CTRL_28") (class "Default")
      (node (ref "D28") (pin "2") (pinfunction "A2_2") (pintype "passive"))
      (node (ref "R52") (pin "1") (pinfunction "1_1") (pintype "passive"))
      (node (ref "SV1") (pin "26") (pinfunction "26_26") (pintype "passive"))
      (node (ref "U$4") (pin "I/O3") (pinfunction "15_I/O3") (pintype "bidirectional"))
    )
    (net (code "38") (name "CTRL_29") (class "Default")
      (node (ref "D29") (pin "2") (pinfunction "A2_2") (pintype "passive"))
      (node (ref "R51") (pin "1") (pinfunction "1_1") (pintype "passive"))
      (node (ref "SV1") (pin "28") (pinfunction "28_28") (pintype "passive"))
      (node (ref "U$4") (pin "I/O4") (pinfunction "16_I/O4") (pintype "bidirectional"))
    )
    (net (code "39") (name "CTRL_30") (class "Default")
      (node (ref "D30") (pin "2") (pinfunction "A2_2") (pintype "passive"))
      (node (ref "R50") (pin "1") (pinfunction "1_1") (pintype "passive"))
      (node (ref "SV1") (pin "30") (pinfunction "30_30") (pintype "passive"))
      (node (ref "U$4") (pin "I/O5") (pinfunction "17_I/O5") (pintype "bidirectional"))
    )
    (net (code "40") (name "CTRL_31") (class "Default")
      (node (ref "D31") (pin "2") (pinfunction "A2_2") (pintype "passive"))
      (node (ref "R49") (pin "1") (pinfunction "1_1") (pintype "passive"))
      (node (ref "SV1") (pin "32") (pinfunction "32_32") (pintype "passive"))
      (node (ref "U$4") (pin "I/O6") (pinfunction "18_I/O6") (pintype "bidirectional"))
    )
    (net (code "41") (name "CTRL_32") (class "Default")
      (node (ref "D32") (pin "2") (pinfunction "A2_2") (pintype "passive"))
      (node (ref "IC5") (pin "13") (pinfunction "I1_13") (pintype "input"))
      (node (ref "R48") (pin "1") (pinfunction "1_1") (pintype "passive"))
      (node (ref "SV1") (pin "34") (pinfunction "34_34") (pintype "passive"))
      (node (ref "U$4") (pin "I/O7") (pinfunction "19_I/O7") (pintype "bidirectional"))
    )
    (net (code "42") (name "CTRL_MW") (class "Default")
      (node (ref "SV2") (pin "19") (pinfunction "19_19") (pintype "passive"))
      (node (ref "U$1") (pin "!OE") (pinfunction "22_!OE") (pintype "bidirectional"))
      (node (ref "U$2") (pin "!OE") (pinfunction "22_!OE") (pintype "bidirectional"))
      (node (ref "U$3") (pin "!OE") (pinfunction "22_!OE") (pintype "bidirectional"))
      (node (ref "U$4") (pin "!OE") (pinfunction "22_!OE") (pintype "bidirectional"))
    )
    (net (code "43") (name "FLAG_1") (class "Default")
      (node (ref "D44") (pin "A") (pinfunction "A_A") (pintype "passive"))
      (node (ref "IC3") (pin "3") (pinfunction "Q1_3") (pintype "tri_state"))
      (node (ref "R91") (pin "1") (pinfunction "1_1") (pintype "passive"))
      (node (ref "SV2") (pin "13") (pinfunction "13_13") (pintype "passive"))
      (node (ref "U$1") (pin "A11") (pinfunction "23_A11") (pintype "bidirectional"))
      (node (ref "U$2") (pin "A11") (pinfunction "23_A11") (pintype "bidirectional"))
      (node (ref "U$3") (pin "A11") (pinfunction "23_A11") (pintype "bidirectional"))
      (node (ref "U$4") (pin "A11") (pinfunction "23_A11") (pintype "bidirectional"))
    )
    (net (code "44") (name "FLAG_2") (class "Default")
      (node (ref "D45") (pin "A") (pinfunction "A_A") (pintype "passive"))
      (node (ref "IC3") (pin "4") (pinfunction "Q2_4") (pintype "tri_state"))
      (node (ref "R92") (pin "1") (pinfunction "1_1") (pintype "passive"))
      (node (ref "SV2") (pin "11") (pinfunction "11_11") (pintype "passive"))
      (node (ref "U$1") (pin "A12") (pinfunction "2_A12") (pintype "bidirectional"))
      (node (ref "U$2") (pin "A12") (pinfunction "2_A12") (pintype "bidirectional"))
      (node (ref "U$3") (pin "A12") (pinfunction "2_A12") (pintype "bidirectional"))
      (node (ref "U$4") (pin "A12") (pinfunction "2_A12") (pintype "bidirectional"))
    )
    (net (code "45") (name "FLAG_3") (class "Default")
      (node (ref "D46") (pin "A") (pinfunction "A_A") (pintype "passive"))
      (node (ref "IC3") (pin "5") (pinfunction "Q3_5") (pintype "tri_state"))
      (node (ref "R93") (pin "1") (pinfunction "1_1") (pintype "passive"))
      (node (ref "SV2") (pin "9") (pinfunction "9_9") (pintype "passive"))
      (node (ref "U$1") (pin "A13") (pinfunction "26_A13") (pintype "bidirectional"))
      (node (ref "U$2") (pin "A13") (pinfunction "26_A13") (pintype "bidirectional"))
      (node (ref "U$3") (pin "A13") (pinfunction "26_A13") (pintype "bidirectional"))
      (node (ref "U$4") (pin "A13") (pinfunction "26_A13") (pintype "bidirectional"))
    )
    (net (code "46") (name "FLAG_4") (class "Default")
      (node (ref "D47") (pin "A") (pinfunction "A_A") (pintype "passive"))
      (node (ref "IC3") (pin "6") (pinfunction "Q4_6") (pintype "tri_state"))
      (node (ref "R94") (pin "1") (pinfunction "1_1") (pintype "passive"))
      (node (ref "SV2") (pin "7") (pinfunction "7_7") (pintype "passive"))
      (node (ref "U$1") (pin "A14") (pinfunction "1_A14") (pintype "bidirectional"))
      (node (ref "U$2") (pin "A14") (pinfunction "1_A14") (pintype "bidirectional"))
      (node (ref "U$3") (pin "A14") (pinfunction "1_A14") (pintype "bidirectional"))
      (node (ref "U$4") (pin "A14") (pinfunction "1_A14") (pintype "bidirectional"))
    )
    (net (code "47") (name "GND") (class "Default")
      (node (ref "C1") (pin "2") (pinfunction "2_2") (pintype "passive"))
      (node (ref "C10") (pin "2") (pinfunction "2_2") (pintype "passive"))
      (node (ref "C11") (pin "2") (pinfunction "2_2") (pintype "passive"))
      (node (ref "C12") (pin "2") (pinfunction "2_2") (pintype "passive"))
      (node (ref "C13") (pin "2") (pinfunction "2_2") (pintype "passive"))
      (node (ref "C14") (pin "2") (pinfunction "2_2") (pintype "passive"))
      (node (ref "C2") (pin "2") (pinfunction "2_2") (pintype "passive"))
      (node (ref "C3") (pin "2") (pinfunction "2_2") (pintype "passive"))
      (node (ref "C4") (pin "2") (pinfunction "2_2") (pintype "passive"))
      (node (ref "C5") (pin "2") (pinfunction "2_2") (pintype "passive"))
      (node (ref "C6") (pin "2") (pinfunction "2_2") (pintype "passive"))
      (node (ref "C7") (pin "2") (pinfunction "2_2") (pintype "passive"))
      (node (ref "C8") (pin "2") (pinfunction "2_2") (pintype "passive"))
      (node (ref "C9") (pin "2") (pinfunction "2_2") (pintype "passive"))
      (node (ref "IC1") (pin "1") (pinfunction "M_1") (pintype "input"))
      (node (ref "IC1") (pin "2") (pinfunction "N_2") (pintype "input"))
      (node (ref "IC1") (pin "8") (pinfunction "GND_8") (pintype "power_in"))
      (node (ref "IC2") (pin "1") (pinfunction "M_1") (pintype "input"))
      (node (ref "IC2") (pin "2") (pinfunction "N_2") (pintype "input"))
      (node (ref "IC2") (pin "8") (pinfunction "GND_8") (pintype "power_in"))
      (node (ref "IC3") (pin "1") (pinfunction "M_1") (pintype "input"))
      (node (ref "IC3") (pin "2") (pinfunction "N_2") (pintype "input"))
      (node (ref "IC3") (pin "8") (pinfunction "GND_8") (pintype "power_in"))
      (node (ref "IC4") (pin "7") (pinfunction "GND_7") (pintype "power_in"))
      (node (ref "IC5") (pin "7") (pinfunction "GND_7") (pintype "power_in"))
      (node (ref "R1") (pin "1") (pinfunction "1_1") (pintype "passive"))
      (node (ref "R10") (pin "1") (pinfunction "1_1") (pintype "passive"))
      (node (ref "R11") (pin "1") (pinfunction "1_1") (pintype "passive"))
      (node (ref "R12") (pin "1") (pinfunction "1_1") (pintype "passive"))
      (node (ref "R13") (pin "1") (pinfunction "1_1") (pintype "passive"))
      (node (ref "R14") (pin "1") (pinfunction "1_1") (pintype "passive"))
      (node (ref "R15") (pin "1") (pinfunction "1_1") (pintype "passive"))
      (node (ref "R16") (pin "1") (pinfunction "1_1") (pintype "passive"))
      (node (ref "R17") (pin "1") (pinfunction "1_1") (pintype "passive"))
      (node (ref "R18") (pin "1") (pinfunction "1_1") (pintype "passive"))
      (node (ref "R19") (pin "1") (pinfunction "1_1") (pintype "passive"))
      (node (ref "R2") (pin "1") (pinfunction "1_1") (pintype "passive"))
      (node (ref "R20") (pin "1") (pinfunction "1_1") (pintype "passive"))
      (node (ref "R21") (pin "1") (pinfunction "1_1") (pintype "passive"))
      (node (ref "R22") (pin "1") (pinfunction "1_1") (pintype "passive"))
      (node (ref "R23") (pin "1") (pinfunction "1_1") (pintype "passive"))
      (node (ref "R24") (pin "1") (pinfunction "1_1") (pintype "passive"))
      (node (ref "R25") (pin "1") (pinfunction "1_1") (pintype "passive"))
      (node (ref "R26") (pin "1") (pinfunction "1_1") (pintype "passive"))
      (node (ref "R27") (pin "1") (pinfunction "1_1") (pintype "passive"))
      (node (ref "R28") (pin "1") (pinfunction "1_1") (pintype "passive"))
      (node (ref "R29") (pin "1") (pinfunction "1_1") (pintype "passive"))
      (node (ref "R3") (pin "1") (pinfunction "1_1") (pintype "passive"))
      (node (ref "R30") (pin "1") (pinfunction "1_1") (pintype "passive"))
      (node (ref "R31") (pin "1") (pinfunction "1_1") (pintype "passive"))
      (node (ref "R32") (pin "1") (pinfunction "1_1") (pintype "passive"))
      (node (ref "R33") (pin "1") (pinfunction "1_1") (pintype "passive"))
      (node (ref "R34") (pin "1") (pinfunction "1_1") (pintype "passive"))
      (node (ref "R35") (pin "1") (pinfunction "1_1") (pintype "passive"))
      (node (ref "R36") (pin "1") (pinfunction "1_1") (pintype "passive"))
      (node (ref "R37") (pin "1") (pinfunction "1_1") (pintype "passive"))
      (node (ref "R38") (pin "1") (pinfunction "1_1") (pintype "passive"))
      (node (ref "R39") (pin "1") (pinfunction "1_1") (pintype "passive"))
      (node (ref "R4") (pin "1") (pinfunction "1_1") (pintype "passive"))
      (node (ref "R40") (pin "1") (pinfunction "1_1") (pintype "passive"))
      (node (ref "R41") (pin "1") (pinfunction "1_1") (pintype "passive"))
      (node (ref "R42") (pin "1") (pinfunction "1_1") (pintype "passive"))
      (node (ref "R43") (pin "1") (pinfunction "1_1") (pintype "passive"))
      (node (ref "R44") (pin "1") (pinfunction "1_1") (pintype "passive"))
      (node (ref "R45") (pin "1") (pinfunction "1_1") (pintype "passive"))
      (node (ref "R46") (pin "1") (pinfunction "1_1") (pintype "passive"))
      (node (ref "R47") (pin "1") (pinfunction "1_1") (pintype "passive"))
      (node (ref "R48") (pin "2") (pinfunction "2_2") (pintype "passive"))
      (node (ref "R49") (pin "2") (pinfunction "2_2") (pintype "passive"))
      (node (ref "R5") (pin "1") (pinfunction "1_1") (pintype "passive"))
      (node (ref "R50") (pin "2") (pinfunction "2_2") (pintype "passive"))
      (node (ref "R51") (pin "2") (pinfunction "2_2") (pintype "passive"))
      (node (ref "R52") (pin "2") (pinfunction "2_2") (pintype "passive"))
      (node (ref "R53") (pin "2") (pinfunction "2_2") (pintype "passive"))
      (node (ref "R54") (pin "2") (pinfunction "2_2") (pintype "passive"))
      (node (ref "R55") (pin "2") (pinfunction "2_2") (pintype "passive"))
      (node (ref "R56") (pin "2") (pinfunction "2_2") (pintype "passive"))
      (node (ref "R57") (pin "2") (pinfunction "2_2") (pintype "passive"))
      (node (ref "R58") (pin "2") (pinfunction "2_2") (pintype "passive"))
      (node (ref "R59") (pin "2") (pinfunction "2_2") (pintype "passive"))
      (node (ref "R6") (pin "1") (pinfunction "1_1") (pintype "passive"))
      (node (ref "R60") (pin "2") (pinfunction "2_2") (pintype "passive"))
      (node (ref "R61") (pin "2") (pinfunction "2_2") (pintype "passive"))
      (node (ref "R62") (pin "2") (pinfunction "2_2") (pintype "passive"))
      (node (ref "R63") (pin "2") (pinfunction "2_2") (pintype "passive"))
      (node (ref "R64") (pin "2") (pinfunction "2_2") (pintype "passive"))
      (node (ref "R65") (pin "2") (pinfunction "2_2") (pintype "passive"))
      (node (ref "R66") (pin "2") (pinfunction "2_2") (pintype "passive"))
      (node (ref "R67") (pin "2") (pinfunction "2_2") (pintype "passive"))
      (node (ref "R68") (pin "2") (pinfunction "2_2") (pintype "passive"))
      (node (ref "R69") (pin "2") (pinfunction "2_2") (pintype "passive"))
      (node (ref "R7") (pin "1") (pinfunction "1_1") (pintype "passive"))
      (node (ref "R70") (pin "2") (pinfunction "2_2") (pintype "passive"))
      (node (ref "R71") (pin "2") (pinfunction "2_2") (pintype "passive"))
      (node (ref "R72") (pin "2") (pinfunction "2_2") (pintype "passive"))
      (node (ref "R73") (pin "2") (pinfunction "2_2") (pintype "passive"))
      (node (ref "R74") (pin "2") (pinfunction "2_2") (pintype "passive"))
      (node (ref "R75") (pin "2") (pinfunction "2_2") (pintype "passive"))
      (node (ref "R76") (pin "2") (pinfunction "2_2") (pintype "passive"))
      (node (ref "R77") (pin "2") (pinfunction "2_2") (pintype "passive"))
      (node (ref "R78") (pin "2") (pinfunction "2_2") (pintype "passive"))
      (node (ref "R79") (pin "2") (pinfunction "2_2") (pintype "passive"))
      (node (ref "R8") (pin "1") (pinfunction "1_1") (pintype "passive"))
      (node (ref "R80") (pin "2") (pinfunction "2_2") (pintype "passive"))
      (node (ref "R81") (pin "2") (pinfunction "2_2") (pintype "passive"))
      (node (ref "R82") (pin "2") (pinfunction "2_2") (pintype "passive"))
      (node (ref "R83") (pin "2") (pinfunction "2_2") (pintype "passive"))
      (node (ref "R84") (pin "2") (pinfunction "2_2") (pintype "passive"))
      (node (ref "R85") (pin "2") (pinfunction "2_2") (pintype "passive"))
      (node (ref "R86") (pin "2") (pinfunction "2_2") (pintype "passive"))
      (node (ref "R87") (pin "2") (pinfunction "2_2") (pintype "passive"))
      (node (ref "R88") (pin "2") (pinfunction "2_2") (pintype "passive"))
      (node (ref "R89") (pin "2") (pinfunction "2_2") (pintype "passive"))
      (node (ref "R9") (pin "1") (pinfunction "1_1") (pintype "passive"))
      (node (ref "R90") (pin "2") (pinfunction "2_2") (pintype "passive"))
      (node (ref "R91") (pin "2") (pinfunction "2_2") (pintype "passive"))
      (node (ref "R92") (pin "2") (pinfunction "2_2") (pintype "passive"))
      (node (ref "R93") (pin "2") (pinfunction "2_2") (pintype "passive"))
      (node (ref "R94") (pin "2") (pinfunction "2_2") (pintype "passive"))
      (node (ref "R95") (pin "2") (pinfunction "2_2") (pintype "passive"))
      (node (ref "R96") (pin "2") (pinfunction "2_2") (pintype "passive"))
      (node (ref "R97") (pin "2") (pinfunction "2_2") (pintype "passive"))
      (node (ref "SV1") (pin "2") (pinfunction "2_2") (pintype "passive"))
      (node (ref "SV1") (pin "35") (pinfunction "35_35") (pintype "passive"))
      (node (ref "SV2") (pin "2") (pinfunction "2_2") (pintype "passive"))
      (node (ref "SV2") (pin "35") (pinfunction "35_35") (pintype "passive"))
      (node (ref "SV3") (pin "2") (pinfunction "2_2") (pintype "passive"))
      (node (ref "SV3") (pin "35") (pinfunction "35_35") (pintype "passive"))
      (node (ref "SV4") (pin "2") (pinfunction "2_2") (pintype "passive"))
      (node (ref "SV4") (pin "35") (pinfunction "35_35") (pintype "passive"))
      (node (ref "U$1") (pin "!CE") (pinfunction "20_!CE") (pintype "bidirectional"))
      (node (ref "U$1") (pin "GND") (pinfunction "14_GND") (pintype "bidirectional"))
      (node (ref "U$2") (pin "!CE") (pinfunction "20_!CE") (pintype "bidirectional"))
      (node (ref "U$2") (pin "GND") (pinfunction "14_GND") (pintype "bidirectional"))
      (node (ref "U$3") (pin "!CE") (pinfunction "20_!CE") (pintype "bidirectional"))
      (node (ref "U$3") (pin "GND") (pinfunction "14_GND") (pintype "bidirectional"))
      (node (ref "U$4") (pin "!CE") (pinfunction "20_!CE") (pintype "bidirectional"))
      (node (ref "U$4") (pin "GND") (pinfunction "14_GND") (pintype "bidirectional"))
      (node (ref "V1") (pin "8") (pinfunction "-UB_8") (pintype "power_in"))
      (node (ref "V1") (pin "9") (pinfunction "D_9") (pintype "input"))
    )
    (net (code "48") (name "MEMORY_BUS_0") (class "Default")
      (node (ref "IC1") (pin "14") (pinfunction "D1_14") (pintype "input"))
      (node (ref "SV2") (pin "26") (pinfunction "26_26") (pintype "passive"))
    )
    (net (code "49") (name "MEMORY_BUS_1") (class "Default")
      (node (ref "IC1") (pin "13") (pinfunction "D2_13") (pintype "input"))
      (node (ref "SV2") (pin "24") (pinfunction "24_24") (pintype "passive"))
    )
    (net (code "50") (name "MEMORY_BUS_2") (class "Default")
      (node (ref "IC1") (pin "12") (pinfunction "D3_12") (pintype "input"))
      (node (ref "SV2") (pin "22") (pinfunction "22_22") (pintype "passive"))
    )
    (net (code "51") (name "MEMORY_BUS_3") (class "Default")
      (node (ref "IC1") (pin "11") (pinfunction "D4_11") (pintype "input"))
      (node (ref "SV2") (pin "20") (pinfunction "20_20") (pintype "passive"))
    )
    (net (code "52") (name "MEMORY_BUS_4") (class "Default")
      (node (ref "IC2") (pin "14") (pinfunction "D1_14") (pintype "input"))
      (node (ref "SV2") (pin "18") (pinfunction "18_18") (pintype "passive"))
    )
    (net (code "53") (name "MEMORY_BUS_5") (class "Default")
      (node (ref "IC2") (pin "13") (pinfunction "D2_13") (pintype "input"))
      (node (ref "SV2") (pin "16") (pinfunction "16_16") (pintype "passive"))
    )
    (net (code "54") (name "MEMORY_BUS_6") (class "Default")
      (node (ref "IC2") (pin "12") (pinfunction "D3_12") (pintype "input"))
      (node (ref "SV2") (pin "14") (pinfunction "14_14") (pintype "passive"))
    )
    (net (code "55") (name "MEMORY_BUS_7") (class "Default")
      (node (ref "IC2") (pin "11") (pinfunction "D4_11") (pintype "input"))
      (node (ref "SV2") (pin "12") (pinfunction "12_12") (pintype "passive"))
    )
    (net (code "56") (name "Net-(D1-K2)") (class "Default")
      (node (ref "D1") (pin "1") (pinfunction "K2_1") (pintype "passive"))
      (node (ref "R1") (pin "2") (pinfunction "2_2") (pintype "passive"))
    )
    (net (code "57") (name "Net-(D2-K2)") (class "Default")
      (node (ref "D2") (pin "1") (pinfunction "K2_1") (pintype "passive"))
      (node (ref "R2") (pin "2") (pinfunction "2_2") (pintype "passive"))
    )
    (net (code "58") (name "Net-(D3-K2)") (class "Default")
      (node (ref "D3") (pin "1") (pinfunction "K2_1") (pintype "passive"))
      (node (ref "R3") (pin "2") (pinfunction "2_2") (pintype "passive"))
    )
    (net (code "59") (name "Net-(D4-K2)") (class "Default")
      (node (ref "D4") (pin "1") (pinfunction "K2_1") (pintype "passive"))
      (node (ref "R4") (pin "2") (pinfunction "2_2") (pintype "passive"))
    )
    (net (code "60") (name "Net-(D5-K2)") (class "Default")
      (node (ref "D5") (pin "1") (pinfunction "K2_1") (pintype "passive"))
      (node (ref "R5") (pin "2") (pinfunction "2_2") (pintype "passive"))
    )
    (net (code "61") (name "Net-(D6-K2)") (class "Default")
      (node (ref "D6") (pin "1") (pinfunction "K2_1") (pintype "passive"))
      (node (ref "R6") (pin "2") (pinfunction "2_2") (pintype "passive"))
    )
    (net (code "62") (name "Net-(D7-K2)") (class "Default")
      (node (ref "D7") (pin "1") (pinfunction "K2_1") (pintype "passive"))
      (node (ref "R7") (pin "2") (pinfunction "2_2") (pintype "passive"))
    )
    (net (code "63") (name "Net-(D8-K2)") (class "Default")
      (node (ref "D8") (pin "1") (pinfunction "K2_1") (pintype "passive"))
      (node (ref "R8") (pin "2") (pinfunction "2_2") (pintype "passive"))
    )
    (net (code "64") (name "Net-(D9-K2)") (class "Default")
      (node (ref "D9") (pin "1") (pinfunction "K2_1") (pintype "passive"))
      (node (ref "R9") (pin "2") (pinfunction "2_2") (pintype "passive"))
    )
    (net (code "65") (name "Net-(D10-K2)") (class "Default")
      (node (ref "D10") (pin "1") (pinfunction "K2_1") (pintype "passive"))
      (node (ref "R10") (pin "2") (pinfunction "2_2") (pintype "passive"))
    )
    (net (code "66") (name "Net-(D11-K2)") (class "Default")
      (node (ref "D11") (pin "1") (pinfunction "K2_1") (pintype "passive"))
      (node (ref "R11") (pin "2") (pinfunction "2_2") (pintype "passive"))
    )
    (net (code "67") (name "Net-(D12-K2)") (class "Default")
      (node (ref "D12") (pin "1") (pinfunction "K2_1") (pintype "passive"))
      (node (ref "R12") (pin "2") (pinfunction "2_2") (pintype "passive"))
    )
    (net (code "68") (name "Net-(D13-K2)") (class "Default")
      (node (ref "D13") (pin "1") (pinfunction "K2_1") (pintype "passive"))
      (node (ref "R13") (pin "2") (pinfunction "2_2") (pintype "passive"))
    )
    (net (code "69") (name "Net-(D14-K2)") (class "Default")
      (node (ref "D14") (pin "1") (pinfunction "K2_1") (pintype "passive"))
      (node (ref "R14") (pin "2") (pinfunction "2_2") (pintype "passive"))
    )
    (net (code "70") (name "Net-(D15-K2)") (class "Default")
      (node (ref "D15") (pin "1") (pinfunction "K2_1") (pintype "passive"))
      (node (ref "R15") (pin "2") (pinfunction "2_2") (pintype "passive"))
    )
    (net (code "71") (name "Net-(D16-K2)") (class "Default")
      (node (ref "D16") (pin "1") (pinfunction "K2_1") (pintype "passive"))
      (node (ref "R16") (pin "2") (pinfunction "2_2") (pintype "passive"))
    )
    (net (code "72") (name "Net-(D17-K2)") (class "Default")
      (node (ref "D17") (pin "1") (pinfunction "K2_1") (pintype "passive"))
      (node (ref "R17") (pin "2") (pinfunction "2_2") (pintype "passive"))
    )
    (net (code "73") (name "Net-(D18-K2)") (class "Default")
      (node (ref "D18") (pin "1") (pinfunction "K2_1") (pintype "passive"))
      (node (ref "R18") (pin "2") (pinfunction "2_2") (pintype "passive"))
    )
    (net (code "74") (name "Net-(D19-K2)") (class "Default")
      (node (ref "D19") (pin "1") (pinfunction "K2_1") (pintype "passive"))
      (node (ref "R19") (pin "2") (pinfunction "2_2") (pintype "passive"))
    )
    (net (code "75") (name "Net-(D20-K2)") (class "Default")
      (node (ref "D20") (pin "1") (pinfunction "K2_1") (pintype "passive"))
      (node (ref "R20") (pin "2") (pinfunction "2_2") (pintype "passive"))
    )
    (net (code "76") (name "Net-(D21-K2)") (class "Default")
      (node (ref "D21") (pin "1") (pinfunction "K2_1") (pintype "passive"))
      (node (ref "R21") (pin "2") (pinfunction "2_2") (pintype "passive"))
    )
    (net (code "77") (name "Net-(D22-K2)") (class "Default")
      (node (ref "D22") (pin "1") (pinfunction "K2_1") (pintype "passive"))
      (node (ref "R22") (pin "2") (pinfunction "2_2") (pintype "passive"))
    )
    (net (code "78") (name "Net-(D23-K2)") (class "Default")
      (node (ref "D23") (pin "1") (pinfunction "K2_1") (pintype "passive"))
      (node (ref "R23") (pin "2") (pinfunction "2_2") (pintype "passive"))
    )
    (net (code "79") (name "Net-(D24-K2)") (class "Default")
      (node (ref "D24") (pin "1") (pinfunction "K2_1") (pintype "passive"))
      (node (ref "R24") (pin "2") (pinfunction "2_2") (pintype "passive"))
    )
    (net (code "80") (name "Net-(D25-K2)") (class "Default")
      (node (ref "D25") (pin "1") (pinfunction "K2_1") (pintype "passive"))
      (node (ref "R25") (pin "2") (pinfunction "2_2") (pintype "passive"))
    )
    (net (code "81") (name "Net-(D26-K2)") (class "Default")
      (node (ref "D26") (pin "1") (pinfunction "K2_1") (pintype "passive"))
      (node (ref "R26") (pin "2") (pinfunction "2_2") (pintype "passive"))
    )
    (net (code "82") (name "Net-(D27-K2)") (class "Default")
      (node (ref "D27") (pin "1") (pinfunction "K2_1") (pintype "passive"))
      (node (ref "R27") (pin "2") (pinfunction "2_2") (pintype "passive"))
    )
    (net (code "83") (name "Net-(D28-K2)") (class "Default")
      (node (ref "D28") (pin "1") (pinfunction "K2_1") (pintype "passive"))
      (node (ref "R28") (pin "2") (pinfunction "2_2") (pintype "passive"))
    )
    (net (code "84") (name "Net-(D29-K2)") (class "Default")
      (node (ref "D29") (pin "1") (pinfunction "K2_1") (pintype "passive"))
      (node (ref "R29") (pin "2") (pinfunction "2_2") (pintype "passive"))
    )
    (net (code "85") (name "Net-(D30-K2)") (class "Default")
      (node (ref "D30") (pin "1") (pinfunction "K2_1") (pintype "passive"))
      (node (ref "R30") (pin "2") (pinfunction "2_2") (pintype "passive"))
    )
    (net (code "86") (name "Net-(D31-K2)") (class "Default")
      (node (ref "D31") (pin "1") (pinfunction "K2_1") (pintype "passive"))
      (node (ref "R31") (pin "2") (pinfunction "2_2") (pintype "passive"))
    )
    (net (code "87") (name "Net-(D32-K2)") (class "Default")
      (node (ref "D32") (pin "1") (pinfunction "K2_1") (pintype "passive"))
      (node (ref "R32") (pin "2") (pinfunction "2_2") (pintype "passive"))
    )
    (net (code "88") (name "Net-(D33-PadC)") (class "Default")
      (node (ref "D33") (pin "C") (pinfunction "C_C") (pintype "passive"))
      (node (ref "R33") (pin "2") (pinfunction "2_2") (pintype "passive"))
    )
    (net (code "89") (name "Net-(D34-PadC)") (class "Default")
      (node (ref "D34") (pin "C") (pinfunction "C_C") (pintype "passive"))
      (node (ref "R34") (pin "2") (pinfunction "2_2") (pintype "passive"))
    )
    (net (code "90") (name "Net-(D35-PadC)") (class "Default")
      (node (ref "D35") (pin "C") (pinfunction "C_C") (pintype "passive"))
      (node (ref "R35") (pin "2") (pinfunction "2_2") (pintype "passive"))
    )
    (net (code "91") (name "Net-(D36-PadC)") (class "Default")
      (node (ref "D36") (pin "C") (pinfunction "C_C") (pintype "passive"))
      (node (ref "R36") (pin "2") (pinfunction "2_2") (pintype "passive"))
    )
    (net (code "92") (name "Net-(D37-PadC)") (class "Default")
      (node (ref "D37") (pin "C") (pinfunction "C_C") (pintype "passive"))
      (node (ref "R37") (pin "2") (pinfunction "2_2") (pintype "passive"))
    )
    (net (code "93") (name "Net-(D38-PadC)") (class "Default")
      (node (ref "D38") (pin "C") (pinfunction "C_C") (pintype "passive"))
      (node (ref "R38") (pin "2") (pinfunction "2_2") (pintype "passive"))
    )
    (net (code "94") (name "Net-(D39-PadC)") (class "Default")
      (node (ref "D39") (pin "C") (pinfunction "C_C") (pintype "passive"))
      (node (ref "R39") (pin "2") (pinfunction "2_2") (pintype "passive"))
    )
    (net (code "95") (name "Net-(D40-PadC)") (class "Default")
      (node (ref "D40") (pin "C") (pinfunction "C_C") (pintype "passive"))
      (node (ref "R40") (pin "2") (pinfunction "2_2") (pintype "passive"))
    )
    (net (code "96") (name "Net-(D41-PadC)") (class "Default")
      (node (ref "D41") (pin "C") (pinfunction "C_C") (pintype "passive"))
      (node (ref "R41") (pin "2") (pinfunction "2_2") (pintype "passive"))
    )
    (net (code "97") (name "Net-(D42-PadC)") (class "Default")
      (node (ref "D42") (pin "C") (pinfunction "C_C") (pintype "passive"))
      (node (ref "R42") (pin "2") (pinfunction "2_2") (pintype "passive"))
    )
    (net (code "98") (name "Net-(D43-PadC)") (class "Default")
      (node (ref "D43") (pin "C") (pinfunction "C_C") (pintype "passive"))
      (node (ref "R43") (pin "2") (pinfunction "2_2") (pintype "passive"))
    )
    (net (code "99") (name "Net-(D44-PadC)") (class "Default")
      (node (ref "D44") (pin "C") (pinfunction "C_C") (pintype "passive"))
      (node (ref "R44") (pin "2") (pinfunction "2_2") (pintype "passive"))
    )
    (net (code "100") (name "Net-(D45-PadC)") (class "Default")
      (node (ref "D45") (pin "C") (pinfunction "C_C") (pintype "passive"))
      (node (ref "R45") (pin "2") (pinfunction "2_2") (pintype "passive"))
    )
    (net (code "101") (name "Net-(D46-PadC)") (class "Default")
      (node (ref "D46") (pin "C") (pinfunction "C_C") (pintype "passive"))
      (node (ref "R46") (pin "2") (pinfunction "2_2") (pintype "passive"))
    )
    (net (code "102") (name "Net-(D47-PadC)") (class "Default")
      (node (ref "D47") (pin "C") (pinfunction "C_C") (pintype "passive"))
      (node (ref "R47") (pin "2") (pinfunction "2_2") (pintype "passive"))
    )
    (net (code "103") (name "Net-(D48-K2)") (class "Default")
      (node (ref "D48") (pin "1") (pinfunction "K2_1") (pintype "passive"))
      (node (ref "R95") (pin "1") (pinfunction "1_1") (pintype "passive"))
    )
    (net (code "104") (name "Net-(D49-K2)") (class "Default")
      (node (ref "D49") (pin "1") (pinfunction "K2_1") (pintype "passive"))
      (node (ref "R96") (pin "1") (pinfunction "1_1") (pintype "passive"))
    )
    (net (code "105") (name "Net-(IC3A-G1)") (class "Default")
      (node (ref "IC3") (pin "10") (pinfunction "G2_10") (pintype "input"))
      (node (ref "IC3") (pin "9") (pinfunction "G1_9") (pintype "input"))
      (node (ref "IC4") (pin "2") (pinfunction "O_2") (pintype "output"))
    )
    (net (code "106") (name "Net-(IC5A-I0)") (class "Default")
      (node (ref "IC5") (pin "1") (pinfunction "I0_1") (pintype "input"))
      (node (ref "IC5") (pin "11") (pinfunction "O_11") (pintype "output"))
    )
    (net (code "107") (name "Net-(IC5A-I1)") (class "Default")
      (node (ref "IC5") (pin "2") (pinfunction "I1_2") (pintype "input"))
      (node (ref "IC5") (pin "6") (pinfunction "O_6") (pintype "output"))
    )
    (net (code "108") (name "Net-(IC5A-O)") (class "Default")
      (node (ref "IC5") (pin "3") (pinfunction "O_3") (pintype "output"))
      (node (ref "V1") (pin "14") (pinfunction "CLR_14") (pintype "input"))
    )
    (net (code "109") (name "Net-(IC5B-I1)") (class "Default")
      (node (ref "IC5") (pin "5") (pinfunction "I1_5") (pintype "input"))
      (node (ref "V1") (pin "7") (pinfunction "QD_7") (pintype "output"))
    )
    (net (code "110") (name "Net-(IC5D-I0)") (class "Default")
      (node (ref "IC5") (pin "12") (pinfunction "I0_12") (pintype "input"))
      (node (ref "S1") (pin "2") (pinfunction "S1_2") (pintype "passive"))
    )
    (net (code "111") (name "Net-(S1-S)") (class "Default")
      (node (ref "R97") (pin "1") (pinfunction "1_1") (pintype "passive"))
      (node (ref "S1") (pin "1") (pinfunction "S_1") (pintype "passive"))
    )
    (net (code "112") (name "OP-CODE_0") (class "Default")
      (node (ref "D36") (pin "A") (pinfunction "A_A") (pintype "passive"))
      (node (ref "IC1") (pin "3") (pinfunction "Q1_3") (pintype "tri_state"))
      (node (ref "R83") (pin "1") (pinfunction "1_1") (pintype "passive"))
      (node (ref "U$1") (pin "A3") (pinfunction "7_A3") (pintype "bidirectional"))
      (node (ref "U$2") (pin "A3") (pinfunction "7_A3") (pintype "bidirectional"))
      (node (ref "U$3") (pin "A3") (pinfunction "7_A3") (pintype "bidirectional"))
      (node (ref "U$4") (pin "A3") (pinfunction "7_A3") (pintype "bidirectional"))
    )
    (net (code "113") (name "OP-CODE_1") (class "Default")
      (node (ref "D37") (pin "A") (pinfunction "A_A") (pintype "passive"))
      (node (ref "IC1") (pin "4") (pinfunction "Q2_4") (pintype "tri_state"))
      (node (ref "R84") (pin "1") (pinfunction "1_1") (pintype "passive"))
      (node (ref "U$1") (pin "A4") (pinfunction "6_A4") (pintype "bidirectional"))
      (node (ref "U$2") (pin "A4") (pinfunction "6_A4") (pintype "bidirectional"))
      (node (ref "U$3") (pin "A4") (pinfunction "6_A4") (pintype "bidirectional"))
      (node (ref "U$4") (pin "A4") (pinfunction "6_A4") (pintype "bidirectional"))
    )
    (net (code "114") (name "OP-CODE_2") (class "Default")
      (node (ref "D38") (pin "A") (pinfunction "A_A") (pintype "passive"))
      (node (ref "IC1") (pin "5") (pinfunction "Q3_5") (pintype "tri_state"))
      (node (ref "R85") (pin "1") (pinfunction "1_1") (pintype "passive"))
      (node (ref "U$1") (pin "A5") (pinfunction "5_A5") (pintype "bidirectional"))
      (node (ref "U$2") (pin "A5") (pinfunction "5_A5") (pintype "bidirectional"))
      (node (ref "U$3") (pin "A5") (pinfunction "5_A5") (pintype "bidirectional"))
      (node (ref "U$4") (pin "A5") (pinfunction "5_A5") (pintype "bidirectional"))
    )
    (net (code "115") (name "OP-CODE_3") (class "Default")
      (node (ref "D39") (pin "A") (pinfunction "A_A") (pintype "passive"))
      (node (ref "IC1") (pin "6") (pinfunction "Q4_6") (pintype "tri_state"))
      (node (ref "R86") (pin "1") (pinfunction "1_1") (pintype "passive"))
      (node (ref "U$1") (pin "A6") (pinfunction "4_A6") (pintype "bidirectional"))
      (node (ref "U$2") (pin "A6") (pinfunction "4_A6") (pintype "bidirectional"))
      (node (ref "U$3") (pin "A6") (pinfunction "4_A6") (pintype "bidirectional"))
      (node (ref "U$4") (pin "A6") (pinfunction "4_A6") (pintype "bidirectional"))
    )
    (net (code "116") (name "OP-CODE_4") (class "Default")
      (node (ref "D40") (pin "A") (pinfunction "A_A") (pintype "passive"))
      (node (ref "IC2") (pin "3") (pinfunction "Q1_3") (pintype "tri_state"))
      (node (ref "R87") (pin "1") (pinfunction "1_1") (pintype "passive"))
      (node (ref "U$1") (pin "A7") (pinfunction "3_A7") (pintype "bidirectional"))
      (node (ref "U$2") (pin "A7") (pinfunction "3_A7") (pintype "bidirectional"))
      (node (ref "U$3") (pin "A7") (pinfunction "3_A7") (pintype "bidirectional"))
      (node (ref "U$4") (pin "A7") (pinfunction "3_A7") (pintype "bidirectional"))
    )
    (net (code "117") (name "OP-CODE_5") (class "Default")
      (node (ref "D41") (pin "A") (pinfunction "A_A") (pintype "passive"))
      (node (ref "IC2") (pin "4") (pinfunction "Q2_4") (pintype "tri_state"))
      (node (ref "R88") (pin "1") (pinfunction "1_1") (pintype "passive"))
      (node (ref "U$1") (pin "A8") (pinfunction "25_A8") (pintype "bidirectional"))
      (node (ref "U$2") (pin "A8") (pinfunction "25_A8") (pintype "bidirectional"))
      (node (ref "U$3") (pin "A8") (pinfunction "25_A8") (pintype "bidirectional"))
      (node (ref "U$4") (pin "A8") (pinfunction "25_A8") (pintype "bidirectional"))
    )
    (net (code "118") (name "OP-CODE_6") (class "Default")
      (node (ref "D42") (pin "A") (pinfunction "A_A") (pintype "passive"))
      (node (ref "IC2") (pin "5") (pinfunction "Q3_5") (pintype "tri_state"))
      (node (ref "R89") (pin "1") (pinfunction "1_1") (pintype "passive"))
      (node (ref "U$1") (pin "A9") (pinfunction "24_A9") (pintype "bidirectional"))
      (node (ref "U$2") (pin "A9") (pinfunction "24_A9") (pintype "bidirectional"))
      (node (ref "U$3") (pin "A9") (pinfunction "24_A9") (pintype "bidirectional"))
      (node (ref "U$4") (pin "A9") (pinfunction "24_A9") (pintype "bidirectional"))
    )
    (net (code "119") (name "OP-CODE_7") (class "Default")
      (node (ref "D43") (pin "A") (pinfunction "A_A") (pintype "passive"))
      (node (ref "IC2") (pin "6") (pinfunction "Q4_6") (pintype "tri_state"))
      (node (ref "R90") (pin "1") (pinfunction "1_1") (pintype "passive"))
      (node (ref "U$1") (pin "A10") (pinfunction "21_A10") (pintype "bidirectional"))
      (node (ref "U$2") (pin "A10") (pinfunction "21_A10") (pintype "bidirectional"))
      (node (ref "U$3") (pin "A10") (pinfunction "21_A10") (pintype "bidirectional"))
      (node (ref "U$4") (pin "A10") (pinfunction "21_A10") (pintype "bidirectional"))
    )
    (net (code "120") (name "STEP_0") (class "Default")
      (node (ref "D33") (pin "A") (pinfunction "A_A") (pintype "passive"))
      (node (ref "R80") (pin "1") (pinfunction "1_1") (pintype "passive"))
      (node (ref "U$1") (pin "A0") (pinfunction "10_A0") (pintype "bidirectional"))
      (node (ref "U$2") (pin "A0") (pinfunction "10_A0") (pintype "bidirectional"))
      (node (ref "U$3") (pin "A0") (pinfunction "10_A0") (pintype "bidirectional"))
      (node (ref "U$4") (pin "A0") (pinfunction "10_A0") (pintype "bidirectional"))
      (node (ref "V1") (pin "15") (pinfunction "A_15") (pintype "input"))
      (node (ref "V1") (pin "3") (pinfunction "QA_3") (pintype "output"))
    )
    (net (code "121") (name "STEP_1") (class "Default")
      (node (ref "D34") (pin "A") (pinfunction "A_A") (pintype "passive"))
      (node (ref "R81") (pin "1") (pinfunction "1_1") (pintype "passive"))
      (node (ref "U$1") (pin "A1") (pinfunction "9_A1") (pintype "bidirectional"))
      (node (ref "U$2") (pin "A1") (pinfunction "9_A1") (pintype "bidirectional"))
      (node (ref "U$3") (pin "A1") (pinfunction "9_A1") (pintype "bidirectional"))
      (node (ref "U$4") (pin "A1") (pinfunction "9_A1") (pintype "bidirectional"))
      (node (ref "V1") (pin "1") (pinfunction "B_1") (pintype "input"))
      (node (ref "V1") (pin "2") (pinfunction "QB_2") (pintype "output"))
    )
    (net (code "122") (name "STEP_2") (class "Default")
      (node (ref "D35") (pin "A") (pinfunction "A_A") (pintype "passive"))
      (node (ref "R82") (pin "1") (pinfunction "1_1") (pintype "passive"))
      (node (ref "U$1") (pin "A2") (pinfunction "8_A2") (pintype "bidirectional"))
      (node (ref "U$2") (pin "A2") (pinfunction "8_A2") (pintype "bidirectional"))
      (node (ref "U$3") (pin "A2") (pinfunction "8_A2") (pintype "bidirectional"))
      (node (ref "U$4") (pin "A2") (pinfunction "8_A2") (pintype "bidirectional"))
      (node (ref "V1") (pin "10") (pinfunction "C_10") (pintype "input"))
      (node (ref "V1") (pin "6") (pinfunction "QC_6") (pintype "output"))
    )
    (net (code "123") (name "VCC") (class "Default")
      (node (ref "C1") (pin "1") (pinfunction "1_1") (pintype "passive"))
      (node (ref "C10") (pin "1") (pinfunction "1_1") (pintype "passive"))
      (node (ref "C11") (pin "1") (pinfunction "1_1") (pintype "passive"))
      (node (ref "C12") (pin "1") (pinfunction "1_1") (pintype "passive"))
      (node (ref "C13") (pin "1") (pinfunction "1_1") (pintype "passive"))
      (node (ref "C14") (pin "1") (pinfunction "1_1") (pintype "passive"))
      (node (ref "C2") (pin "1") (pinfunction "1_1") (pintype "passive"))
      (node (ref "C3") (pin "1") (pinfunction "1_1") (pintype "passive"))
      (node (ref "C4") (pin "1") (pinfunction "1_1") (pintype "passive"))
      (node (ref "C5") (pin "1") (pinfunction "1_1") (pintype "passive"))
      (node (ref "C6") (pin "1") (pinfunction "1_1") (pintype "passive"))
      (node (ref "C7") (pin "1") (pinfunction "1_1") (pintype "passive"))
      (node (ref "C8") (pin "1") (pinfunction "1_1") (pintype "passive"))
      (node (ref "C9") (pin "1") (pinfunction "1_1") (pintype "passive"))
      (node (ref "IC1") (pin "16") (pinfunction "VCC_16") (pintype "power_in"))
      (node (ref "IC2") (pin "16") (pinfunction "VCC_16") (pintype "power_in"))
      (node (ref "IC3") (pin "16") (pinfunction "VCC_16") (pintype "power_in"))
      (node (ref "IC4") (pin "11") (pinfunction "I_11") (pintype "input"))
      (node (ref "IC4") (pin "13") (pinfunction "I_13") (pintype "input"))
      (node (ref "IC4") (pin "14") (pinfunction "VCC_14") (pintype "power_in"))
      (node (ref "IC4") (pin "3") (pinfunction "I_3") (pintype "input"))
      (node (ref "IC4") (pin "5") (pinfunction "I_5") (pintype "input"))
      (node (ref "IC4") (pin "9") (pinfunction "I_9") (pintype "input"))
      (node (ref "IC5") (pin "10") (pinfunction "I1_10") (pintype "input"))
      (node (ref "IC5") (pin "14") (pinfunction "VCC_14") (pintype "power_in"))
      (node (ref "IC5") (pin "9") (pinfunction "I0_9") (pintype "input"))
      (node (ref "S1") (pin "3") (pinfunction "P_3") (pintype "passive"))
      (node (ref "SV1") (pin "1") (pinfunction "1_1") (pintype "passive"))
      (node (ref "SV1") (pin "36") (pinfunction "36_36") (pintype "passive"))
      (node (ref "SV2") (pin "1") (pinfunction "1_1") (pintype "passive"))
      (node (ref "SV2") (pin "36") (pinfunction "36_36") (pintype "passive"))
      (node (ref "SV3") (pin "1") (pinfunction "1_1") (pintype "passive"))
      (node (ref "SV3") (pin "36") (pinfunction "36_36") (pintype "passive"))
      (node (ref "SV4") (pin "1") (pinfunction "1_1") (pintype "passive"))
      (node (ref "SV4") (pin "36") (pinfunction "36_36") (pintype "passive"))
      (node (ref "U$1") (pin "!WE") (pinfunction "27_!WE") (pintype "bidirectional"))
      (node (ref "U$1") (pin "VCC") (pinfunction "28_VCC") (pintype "bidirectional"))
      (node (ref "U$2") (pin "!WE") (pinfunction "27_!WE") (pintype "bidirectional"))
      (node (ref "U$2") (pin "VCC") (pinfunction "28_VCC") (pintype "bidirectional"))
      (node (ref "U$3") (pin "!WE") (pinfunction "27_!WE") (pintype "bidirectional"))
      (node (ref "U$3") (pin "VCC") (pinfunction "28_VCC") (pintype "bidirectional"))
      (node (ref "U$4") (pin "!WE") (pinfunction "27_!WE") (pintype "bidirectional"))
      (node (ref "U$4") (pin "VCC") (pinfunction "28_VCC") (pintype "bidirectional"))
      (node (ref "V1") (pin "11") (pinfunction "~{LOAD}_11") (pintype "input"))
      (node (ref "V1") (pin "16") (pinfunction "+UB_16") (pintype "power_in"))
      (node (ref "V1") (pin "4") (pinfunction "DOWN_4") (pintype "input"))
    )
    (net (code "124") (name "unconnected-(IC4B-O-Pad4)") (class "Default")
      (node (ref "IC4") (pin "4") (pinfunction "O_4") (pintype "output"))
    )
    (net (code "125") (name "unconnected-(IC4C-O-Pad6)") (class "Default")
      (node (ref "IC4") (pin "6") (pinfunction "O_6") (pintype "output"))
    )
    (net (code "126") (name "unconnected-(IC4D-O-Pad8)") (class "Default")
      (node (ref "IC4") (pin "8") (pinfunction "O_8") (pintype "output"))
    )
    (net (code "127") (name "unconnected-(IC4E-O-Pad10)") (class "Default")
      (node (ref "IC4") (pin "10") (pinfunction "O_10") (pintype "output"))
    )
    (net (code "128") (name "unconnected-(IC4F-O-Pad12)") (class "Default")
      (node (ref "IC4") (pin "12") (pinfunction "O_12") (pintype "output"))
    )
    (net (code "129") (name "unconnected-(IC5C-O-Pad8)") (class "Default")
      (node (ref "IC5") (pin "8") (pinfunction "O_8") (pintype "output"))
    )
    (net (code "130") (name "unconnected-(S1-P1-Pad4)") (class "Default")
      (node (ref "S1") (pin "4") (pinfunction "P1_4") (pintype "passive"))
    )
    (net (code "131") (name "unconnected-(SV2-Pad3)") (class "Default")
      (node (ref "SV2") (pin "3") (pinfunction "3_3") (pintype "passive"))
    )
    (net (code "132") (name "unconnected-(SV2-Pad4)") (class "Default")
      (node (ref "SV2") (pin "4") (pinfunction "4_4") (pintype "passive"))
    )
    (net (code "133") (name "unconnected-(SV2-Pad5)") (class "Default")
      (node (ref "SV2") (pin "5") (pinfunction "5_5") (pintype "passive"))
    )
    (net (code "134") (name "unconnected-(SV2-Pad6)") (class "Default")
      (node (ref "SV2") (pin "6") (pinfunction "6_6") (pintype "passive"))
    )
    (net (code "135") (name "unconnected-(SV2-Pad8)") (class "Default")
      (node (ref "SV2") (pin "8") (pinfunction "8_8") (pintype "passive"))
    )
    (net (code "136") (name "unconnected-(SV2-Pad10)") (class "Default")
      (node (ref "SV2") (pin "10") (pinfunction "10_10") (pintype "passive"))
    )
    (net (code "137") (name "unconnected-(SV2-Pad15)") (class "Default")
      (node (ref "SV2") (pin "15") (pinfunction "15_15") (pintype "passive"))
    )
    (net (code "138") (name "unconnected-(SV2-Pad17)") (class "Default")
      (node (ref "SV2") (pin "17") (pinfunction "17_17") (pintype "passive"))
    )
    (net (code "139") (name "unconnected-(SV2-Pad21)") (class "Default")
      (node (ref "SV2") (pin "21") (pinfunction "21_21") (pintype "passive"))
    )
    (net (code "140") (name "unconnected-(SV2-Pad25)") (class "Default")
      (node (ref "SV2") (pin "25") (pinfunction "25_25") (pintype "passive"))
    )
    (net (code "141") (name "unconnected-(SV3-Pad3)") (class "Default")
      (node (ref "SV3") (pin "3") (pinfunction "3_3") (pintype "passive"))
    )
    (net (code "142") (name "unconnected-(SV3-Pad4)") (class "Default")
      (node (ref "SV3") (pin "4") (pinfunction "4_4") (pintype "passive"))
    )
    (net (code "143") (name "unconnected-(SV3-Pad5)") (class "Default")
      (node (ref "SV3") (pin "5") (pinfunction "5_5") (pintype "passive"))
    )
    (net (code "144") (name "unconnected-(SV3-Pad6)") (class "Default")
      (node (ref "SV3") (pin "6") (pinfunction "6_6") (pintype "passive"))
    )
    (net (code "145") (name "unconnected-(SV3-Pad7)") (class "Default")
      (node (ref "SV3") (pin "7") (pinfunction "7_7") (pintype "passive"))
    )
    (net (code "146") (name "unconnected-(SV3-Pad8)") (class "Default")
      (node (ref "SV3") (pin "8") (pinfunction "8_8") (pintype "passive"))
    )
    (net (code "147") (name "unconnected-(SV3-Pad9)") (class "Default")
      (node (ref "SV3") (pin "9") (pinfunction "9_9") (pintype "passive"))
    )
    (net (code "148") (name "unconnected-(SV3-Pad10)") (class "Default")
      (node (ref "SV3") (pin "10") (pinfunction "10_10") (pintype "passive"))
    )
    (net (code "149") (name "unconnected-(SV3-Pad11)") (class "Default")
      (node (ref "SV3") (pin "11") (pinfunction "11_11") (pintype "passive"))
    )
    (net (code "150") (name "unconnected-(SV3-Pad12)") (class "Default")
      (node (ref "SV3") (pin "12") (pinfunction "12_12") (pintype "passive"))
    )
    (net (code "151") (name "unconnected-(SV3-Pad13)") (class "Default")
      (node (ref "SV3") (pin "13") (pinfunction "13_13") (pintype "passive"))
    )
    (net (code "152") (name "unconnected-(SV3-Pad14)") (class "Default")
      (node (ref "SV3") (pin "14") (pinfunction "14_14") (pintype "passive"))
    )
    (net (code "153") (name "unconnected-(SV3-Pad15)") (class "Default")
      (node (ref "SV3") (pin "15") (pinfunction "15_15") (pintype "passive"))
    )
    (net (code "154") (name "unconnected-(SV3-Pad16)") (class "Default")
      (node (ref "SV3") (pin "16") (pinfunction "16_16") (pintype "passive"))
    )
    (net (code "155") (name "unconnected-(SV3-Pad17)") (class "Default")
      (node (ref "SV3") (pin "17") (pinfunction "17_17") (pintype "passive"))
    )
    (net (code "156") (name "unconnected-(SV3-Pad18)") (class "Default")
      (node (ref "SV3") (pin "18") (pinfunction "18_18") (pintype "passive"))
    )
    (net (code "157") (name "unconnected-(SV3-Pad19)") (class "Default")
      (node (ref "SV3") (pin "19") (pinfunction "19_19") (pintype "passive"))
    )
    (net (code "158") (name "unconnected-(SV3-Pad20)") (class "Default")
      (node (ref "SV3") (pin "20") (pinfunction "20_20") (pintype "passive"))
    )
    (net (code "159") (name "unconnected-(SV3-Pad21)") (class "Default")
      (node (ref "SV3") (pin "21") (pinfunction "21_21") (pintype "passive"))
    )
    (net (code "160") (name "unconnected-(SV3-Pad22)") (class "Default")
      (node (ref "SV3") (pin "22") (pinfunction "22_22") (pintype "passive"))
    )
    (net (code "161") (name "unconnected-(SV3-Pad23)") (class "Default")
      (node (ref "SV3") (pin "23") (pinfunction "23_23") (pintype "passive"))
    )
    (net (code "162") (name "unconnected-(SV3-Pad24)") (class "Default")
      (node (ref "SV3") (pin "24") (pinfunction "24_24") (pintype "passive"))
    )
    (net (code "163") (name "unconnected-(SV3-Pad25)") (class "Default")
      (node (ref "SV3") (pin "25") (pinfunction "25_25") (pintype "passive"))
    )
    (net (code "164") (name "unconnected-(SV3-Pad26)") (class "Default")
      (node (ref "SV3") (pin "26") (pinfunction "26_26") (pintype "passive"))
    )
    (net (code "165") (name "unconnected-(SV3-Pad27)") (class "Default")
      (node (ref "SV3") (pin "27") (pinfunction "27_27") (pintype "passive"))
    )
    (net (code "166") (name "unconnected-(SV3-Pad28)") (class "Default")
      (node (ref "SV3") (pin "28") (pinfunction "28_28") (pintype "passive"))
    )
    (net (code "167") (name "unconnected-(SV3-Pad29)") (class "Default")
      (node (ref "SV3") (pin "29") (pinfunction "29_29") (pintype "passive"))
    )
    (net (code "168") (name "unconnected-(SV3-Pad30)") (class "Default")
      (node (ref "SV3") (pin "30") (pinfunction "30_30") (pintype "passive"))
    )
    (net (code "169") (name "unconnected-(SV3-Pad31)") (class "Default")
      (node (ref "SV3") (pin "31") (pinfunction "31_31") (pintype "passive"))
    )
    (net (code "170") (name "unconnected-(SV3-Pad32)") (class "Default")
      (node (ref "SV3") (pin "32") (pinfunction "32_32") (pintype "passive"))
    )
    (net (code "171") (name "unconnected-(SV3-Pad33)") (class "Default")
      (node (ref "SV3") (pin "33") (pinfunction "33_33") (pintype "passive"))
    )
    (net (code "172") (name "unconnected-(SV3-Pad34)") (class "Default")
      (node (ref "SV3") (pin "34") (pinfunction "34_34") (pintype "passive"))
    )
    (net (code "173") (name "unconnected-(SV4-Pad3)") (class "Default")
      (node (ref "SV4") (pin "3") (pinfunction "3_3") (pintype "passive"))
    )
    (net (code "174") (name "unconnected-(SV4-Pad4)") (class "Default")
      (node (ref "SV4") (pin "4") (pinfunction "4_4") (pintype "passive"))
    )
    (net (code "175") (name "unconnected-(SV4-Pad5)") (class "Default")
      (node (ref "SV4") (pin "5") (pinfunction "5_5") (pintype "passive"))
    )
    (net (code "176") (name "unconnected-(SV4-Pad6)") (class "Default")
      (node (ref "SV4") (pin "6") (pinfunction "6_6") (pintype "passive"))
    )
    (net (code "177") (name "unconnected-(SV4-Pad7)") (class "Default")
      (node (ref "SV4") (pin "7") (pinfunction "7_7") (pintype "passive"))
    )
    (net (code "178") (name "unconnected-(SV4-Pad8)") (class "Default")
      (node (ref "SV4") (pin "8") (pinfunction "8_8") (pintype "passive"))
    )
    (net (code "179") (name "unconnected-(SV4-Pad9)") (class "Default")
      (node (ref "SV4") (pin "9") (pinfunction "9_9") (pintype "passive"))
    )
    (net (code "180") (name "unconnected-(SV4-Pad10)") (class "Default")
      (node (ref "SV4") (pin "10") (pinfunction "10_10") (pintype "passive"))
    )
    (net (code "181") (name "unconnected-(SV4-Pad11)") (class "Default")
      (node (ref "SV4") (pin "11") (pinfunction "11_11") (pintype "passive"))
    )
    (net (code "182") (name "unconnected-(SV4-Pad12)") (class "Default")
      (node (ref "SV4") (pin "12") (pinfunction "12_12") (pintype "passive"))
    )
    (net (code "183") (name "unconnected-(SV4-Pad13)") (class "Default")
      (node (ref "SV4") (pin "13") (pinfunction "13_13") (pintype "passive"))
    )
    (net (code "184") (name "unconnected-(SV4-Pad14)") (class "Default")
      (node (ref "SV4") (pin "14") (pinfunction "14_14") (pintype "passive"))
    )
    (net (code "185") (name "unconnected-(SV4-Pad15)") (class "Default")
      (node (ref "SV4") (pin "15") (pinfunction "15_15") (pintype "passive"))
    )
    (net (code "186") (name "unconnected-(SV4-Pad16)") (class "Default")
      (node (ref "SV4") (pin "16") (pinfunction "16_16") (pintype "passive"))
    )
    (net (code "187") (name "unconnected-(SV4-Pad17)") (class "Default")
      (node (ref "SV4") (pin "17") (pinfunction "17_17") (pintype "passive"))
    )
    (net (code "188") (name "unconnected-(SV4-Pad18)") (class "Default")
      (node (ref "SV4") (pin "18") (pinfunction "18_18") (pintype "passive"))
    )
    (net (code "189") (name "unconnected-(SV4-Pad19)") (class "Default")
      (node (ref "SV4") (pin "19") (pinfunction "19_19") (pintype "passive"))
    )
    (net (code "190") (name "unconnected-(SV4-Pad20)") (class "Default")
      (node (ref "SV4") (pin "20") (pinfunction "20_20") (pintype "passive"))
    )
    (net (code "191") (name "unconnected-(SV4-Pad21)") (class "Default")
      (node (ref "SV4") (pin "21") (pinfunction "21_21") (pintype "passive"))
    )
    (net (code "192") (name "unconnected-(SV4-Pad22)") (class "Default")
      (node (ref "SV4") (pin "22") (pinfunction "22_22") (pintype "passive"))
    )
    (net (code "193") (name "unconnected-(SV4-Pad23)") (class "Default")
      (node (ref "SV4") (pin "23") (pinfunction "23_23") (pintype "passive"))
    )
    (net (code "194") (name "unconnected-(SV4-Pad24)") (class "Default")
      (node (ref "SV4") (pin "24") (pinfunction "24_24") (pintype "passive"))
    )
    (net (code "195") (name "unconnected-(SV4-Pad25)") (class "Default")
      (node (ref "SV4") (pin "25") (pinfunction "25_25") (pintype "passive"))
    )
    (net (code "196") (name "unconnected-(SV4-Pad26)") (class "Default")
      (node (ref "SV4") (pin "26") (pinfunction "26_26") (pintype "passive"))
    )
    (net (code "197") (name "unconnected-(SV4-Pad27)") (class "Default")
      (node (ref "SV4") (pin "27") (pinfunction "27_27") (pintype "passive"))
    )
    (net (code "198") (name "unconnected-(SV4-Pad28)") (class "Default")
      (node (ref "SV4") (pin "28") (pinfunction "28_28") (pintype "passive"))
    )
    (net (code "199") (name "unconnected-(SV4-Pad29)") (class "Default")
      (node (ref "SV4") (pin "29") (pinfunction "29_29") (pintype "passive"))
    )
    (net (code "200") (name "unconnected-(SV4-Pad30)") (class "Default")
      (node (ref "SV4") (pin "30") (pinfunction "30_30") (pintype "passive"))
    )
    (net (code "201") (name "unconnected-(SV4-Pad31)") (class "Default")
      (node (ref "SV4") (pin "31") (pinfunction "31_31") (pintype "passive"))
    )
    (net (code "202") (name "unconnected-(SV4-Pad32)") (class "Default")
      (node (ref "SV4") (pin "32") (pinfunction "32_32") (pintype "passive"))
    )
    (net (code "203") (name "unconnected-(SV4-Pad33)") (class "Default")
      (node (ref "SV4") (pin "33") (pinfunction "33_33") (pintype "passive"))
    )
    (net (code "204") (name "unconnected-(SV4-Pad34)") (class "Default")
      (node (ref "SV4") (pin "34") (pinfunction "34_34") (pintype "passive"))
    )
    (net (code "205") (name "unconnected-(V1C-~{BO}-Pad13)") (class "Default")
      (node (ref "V1") (pin "13") (pinfunction "~{BO}_13") (pintype "output"))
    )
    (net (code "206") (name "unconnected-(V1C-~{CO}-Pad12)") (class "Default")
      (node (ref "V1") (pin "12") (pinfunction "~{CO}_12") (pintype "output"))
    )
  )
)
